# moire_v2_7.net
KiCad netlist of a schematic drawn in EAGLE
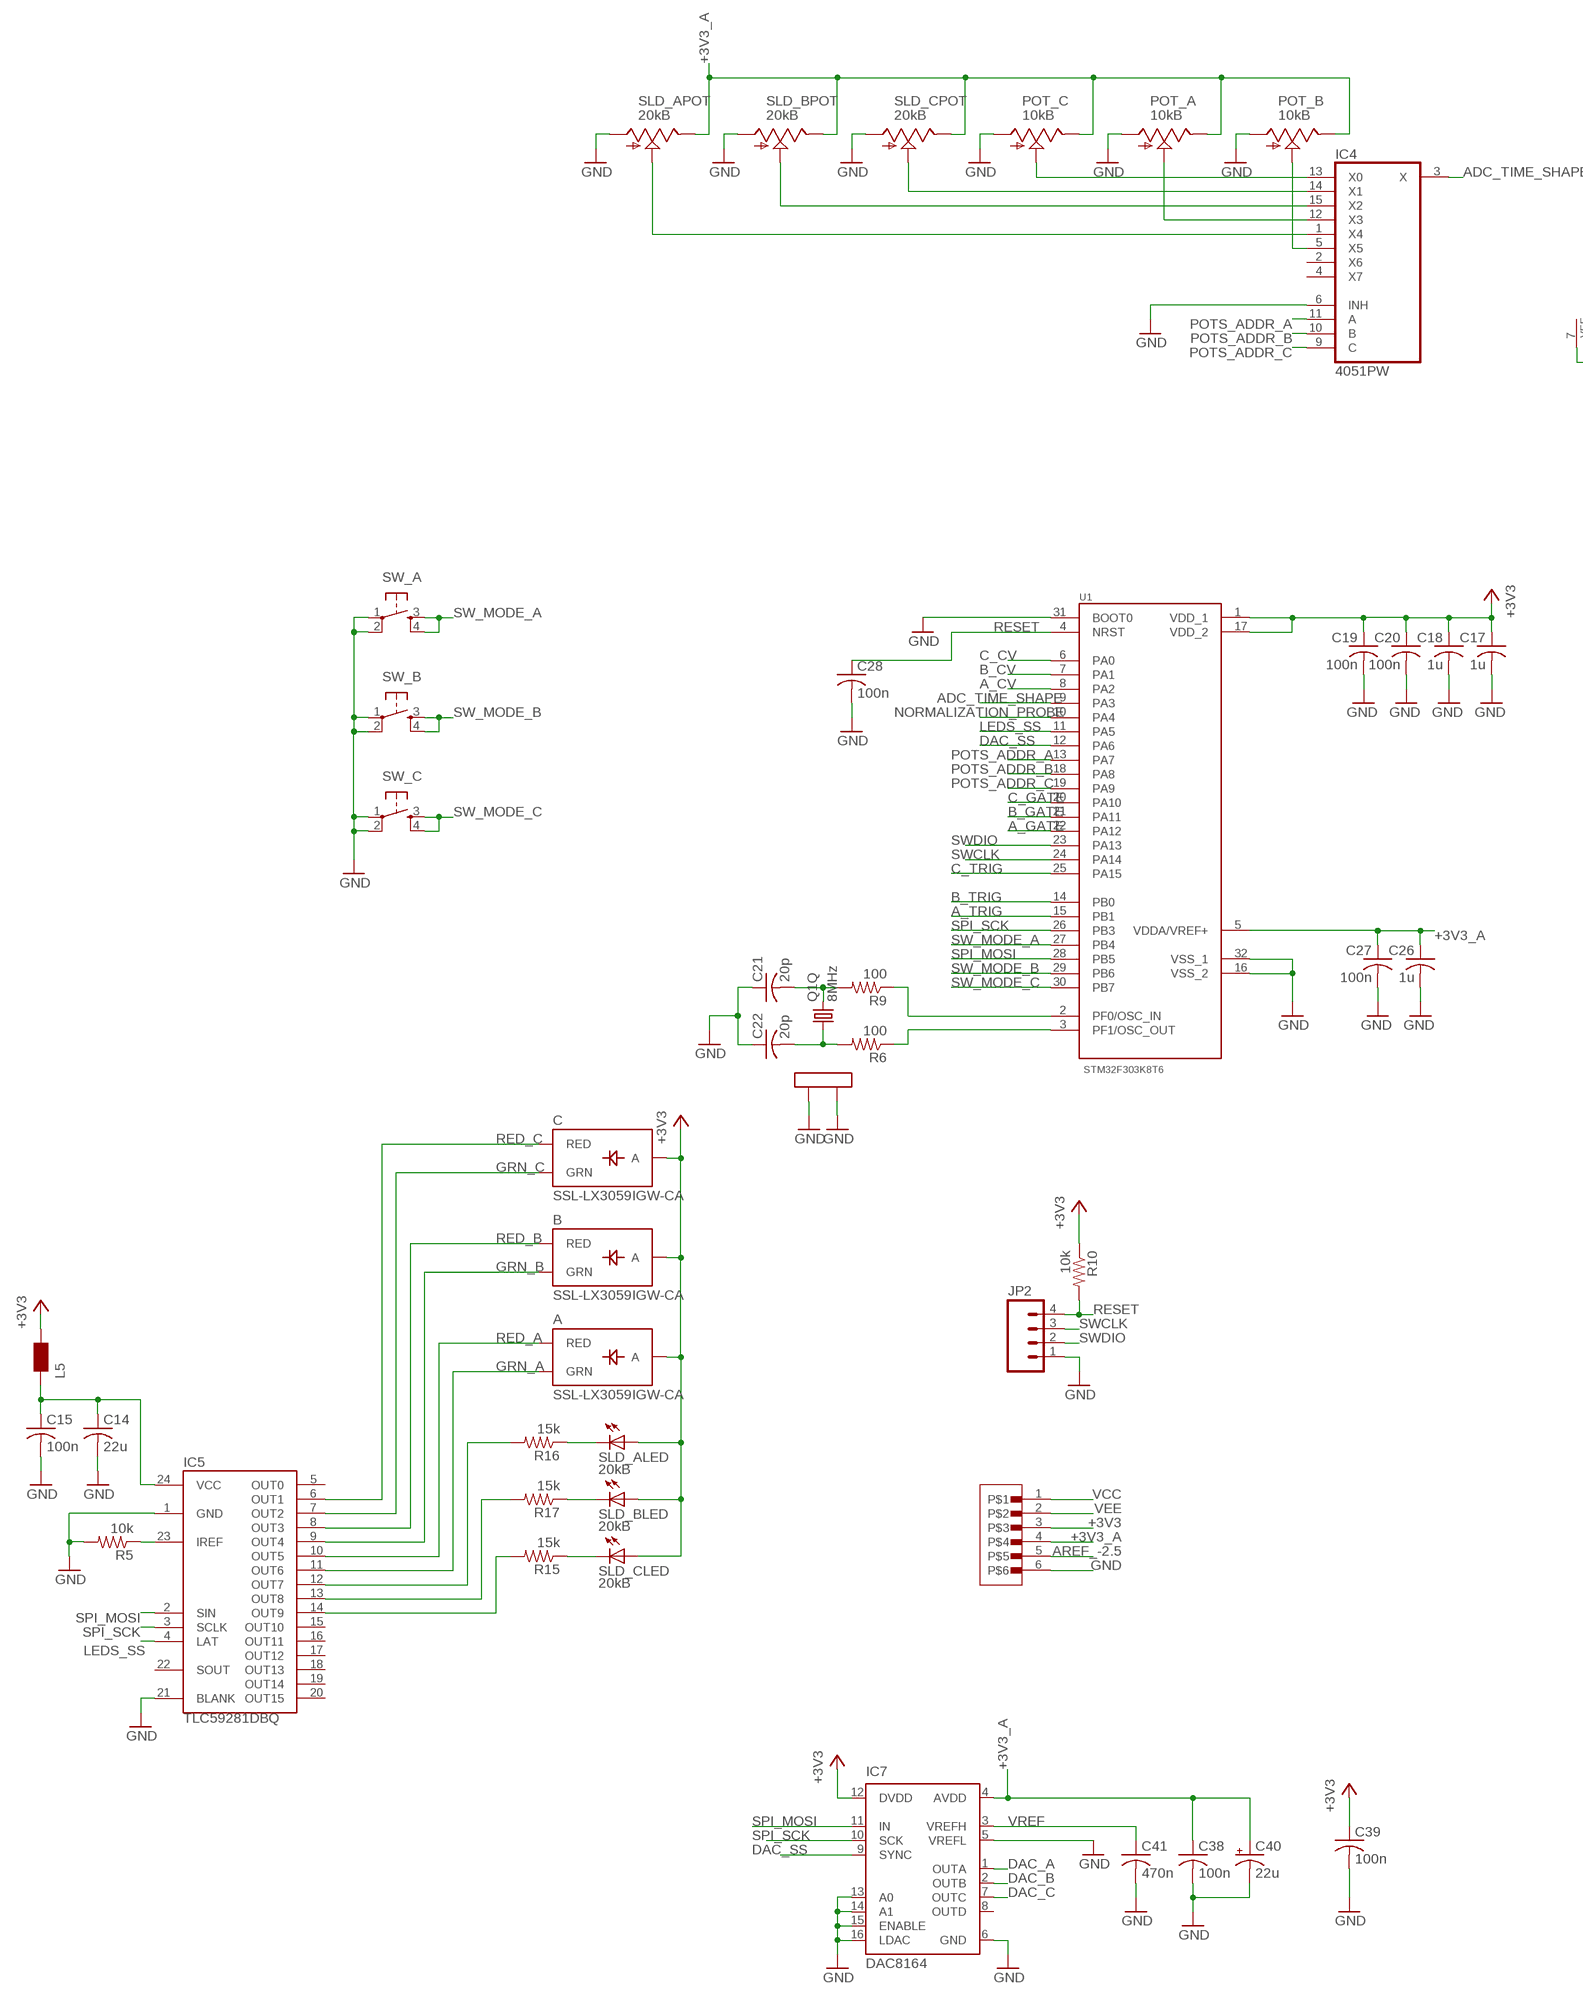
[diagram p0: schematic, sheet 1, part 1 of 2]
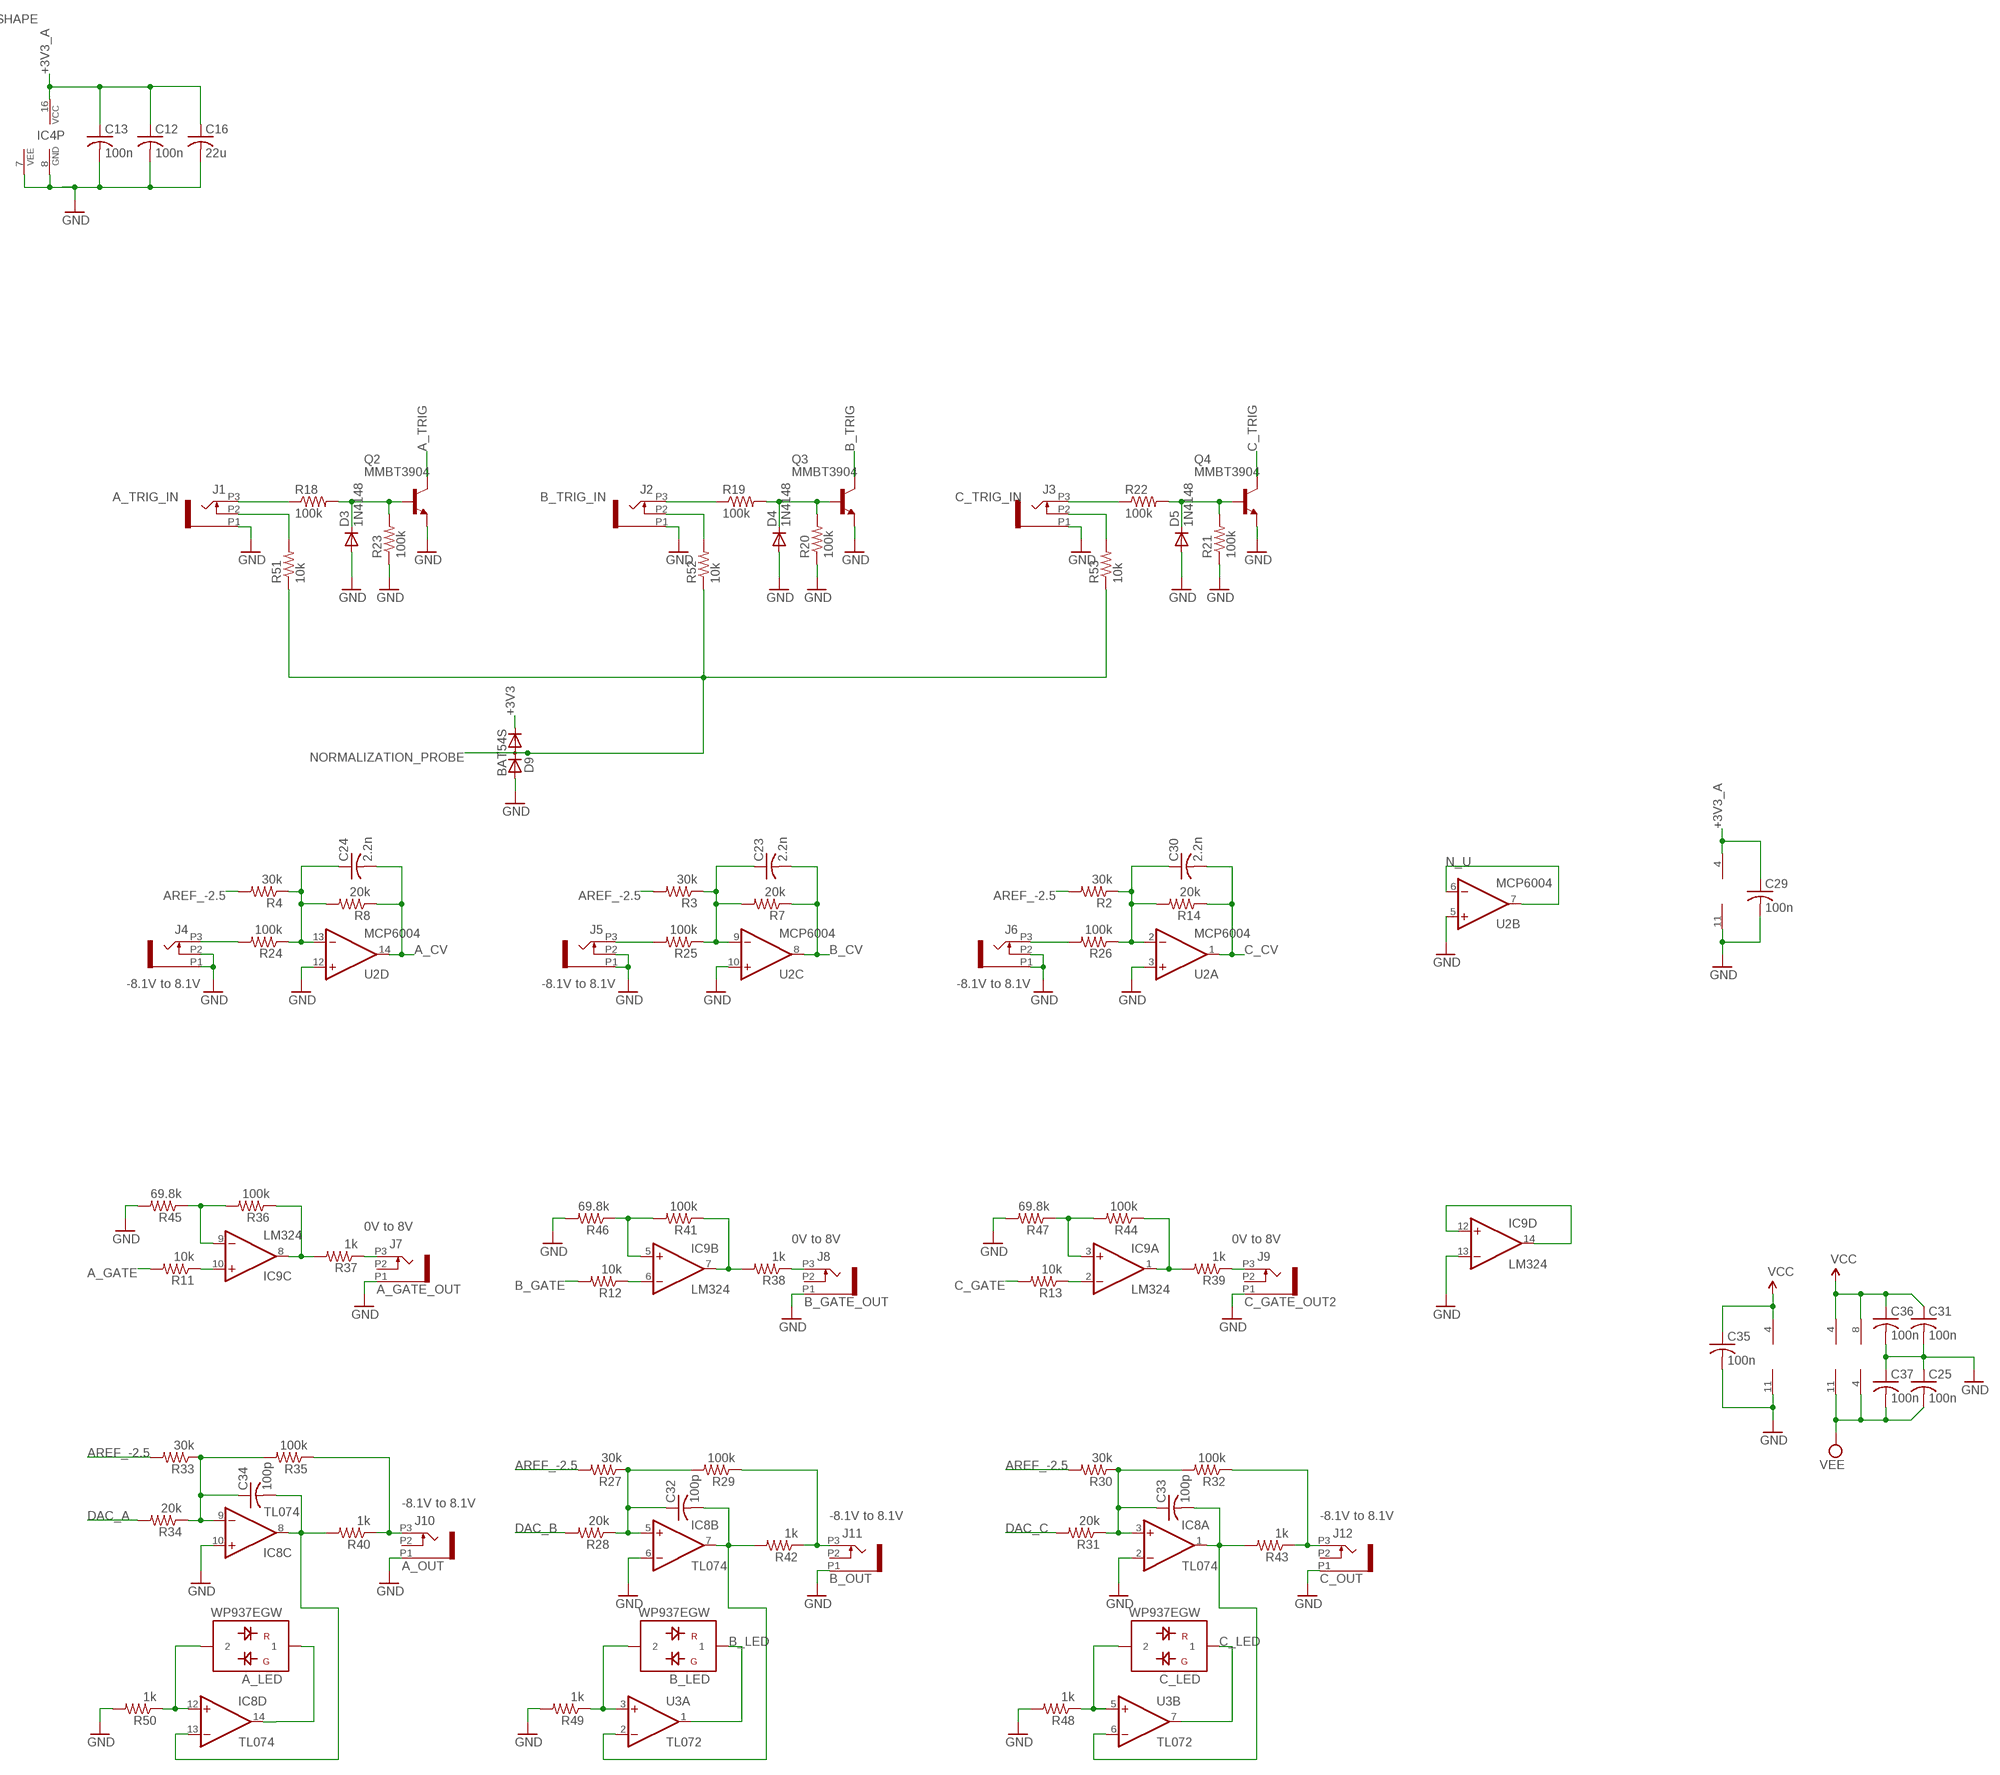
[diagram p1: schematic, sheet 1, part 2 of 2]
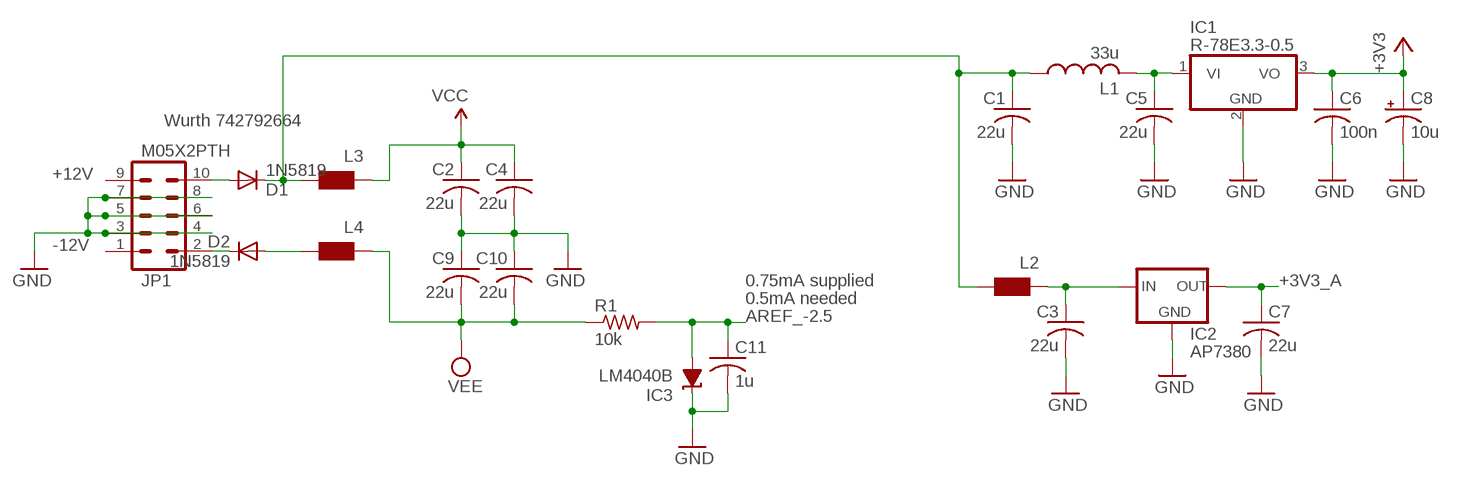
[diagram p2: schematic, sheet 2]

(export (version "E")
  (design (tool "Eeschema 10.0.6"))
  (components
    (comp (ref "A")
      (value "SSL-LX3059IGW-CA")
      (footprint "eagle-import:LED-BICOLOR-THROUGHHOLE-LUMEX")
      (libsource (lib "eagle-import") (part "LED-BICOLOR-THROUGHHOLE-CA"))
    )
    (comp (ref "A_LED")
      (value "WP937EGW")
      (footprint "eagle-import:LED3MM")
      (libsource (lib "eagle-import") (part "LED-BICOLOR-SHARED-THROUGHHOLE"))
    )
    (comp (ref "B")
      (value "SSL-LX3059IGW-CA")
      (footprint "eagle-import:LED-BICOLOR-THROUGHHOLE-LUMEX")
      (libsource (lib "eagle-import") (part "LED-BICOLOR-THROUGHHOLE-CA"))
    )
    (comp (ref "B_LED")
      (value "WP937EGW")
      (footprint "eagle-import:LED3MM")
      (libsource (lib "eagle-import") (part "LED-BICOLOR-SHARED-THROUGHHOLE"))
    )
    (comp (ref "C")
      (value "SSL-LX3059IGW-CA")
      (footprint "eagle-import:LED-BICOLOR-THROUGHHOLE-LUMEX")
      (libsource (lib "eagle-import") (part "LED-BICOLOR-THROUGHHOLE-CA"))
    )
    (comp (ref "C12")
      (value "100n")
      (footprint "eagle-import:RCL_C0603")
      (libsource (lib "eagle-import") (part "RCL_C-USC0603"))
    )
    (comp (ref "C13")
      (value "100n")
      (footprint "eagle-import:RCL_C0603")
      (libsource (lib "eagle-import") (part "RCL_C-USC0603"))
    )
    (comp (ref "C14")
      (value "22u")
      (footprint "eagle-import:RCL_C1206")
      (libsource (lib "eagle-import") (part "RCL_C-USC1206"))
    )
    (comp (ref "C15")
      (value "100n")
      (footprint "eagle-import:RCL_C0603")
      (libsource (lib "eagle-import") (part "RCL_C-USC0603"))
    )
    (comp (ref "C16")
      (value "22u")
      (footprint "eagle-import:RCL_C1206")
      (libsource (lib "eagle-import") (part "RCL_C-USC1206"))
    )
    (comp (ref "C17")
      (value "1u")
      (footprint "eagle-import:RCL_C0603")
      (libsource (lib "eagle-import") (part "RCL_C-USC0603"))
    )
    (comp (ref "C18")
      (value "1u")
      (footprint "eagle-import:RCL_C0603")
      (libsource (lib "eagle-import") (part "RCL_C-USC0603"))
    )
    (comp (ref "C19")
      (value "100n")
      (footprint "eagle-import:RCL_C0603")
      (libsource (lib "eagle-import") (part "RCL_C-USC0603"))
    )
    (comp (ref "C20")
      (value "100n")
      (footprint "eagle-import:RCL_C0603")
      (libsource (lib "eagle-import") (part "RCL_C-USC0603"))
    )
    (comp (ref "C21")
      (value "20p")
      (footprint "eagle-import:RCL_C0603")
      (libsource (lib "eagle-import") (part "RCL_C-USC0603"))
    )
    (comp (ref "C22")
      (value "20p")
      (footprint "eagle-import:RCL_C0603")
      (libsource (lib "eagle-import") (part "RCL_C-USC0603"))
    )
    (comp (ref "C23")
      (value "2.2n")
      (footprint "eagle-import:RCL_C0603")
      (libsource (lib "eagle-import") (part "RCL_C-USC0603"))
    )
    (comp (ref "C24")
      (value "2.2n")
      (footprint "eagle-import:RCL_C0603")
      (libsource (lib "eagle-import") (part "RCL_C-USC0603"))
    )
    (comp (ref "C25")
      (value "100n")
      (footprint "eagle-import:RCL_C0603")
      (libsource (lib "eagle-import") (part "RCL_C-USC0603"))
    )
    (comp (ref "C26")
      (value "1u")
      (footprint "eagle-import:RCL_C0603")
      (libsource (lib "eagle-import") (part "RCL_C-USC0603"))
    )
    (comp (ref "C27")
      (value "100n")
      (footprint "eagle-import:RCL_C0603")
      (libsource (lib "eagle-import") (part "RCL_C-USC0603"))
    )
    (comp (ref "C28")
      (value "100n")
      (footprint "eagle-import:RCL_C0603")
      (libsource (lib "eagle-import") (part "RCL_C-USC0603"))
    )
    (comp (ref "C29")
      (value "100n")
      (footprint "eagle-import:RCL_C0603")
      (libsource (lib "eagle-import") (part "RCL_C-USC0603"))
    )
    (comp (ref "C30")
      (value "2.2n")
      (footprint "eagle-import:RCL_C0603")
      (libsource (lib "eagle-import") (part "RCL_C-USC0603"))
    )
    (comp (ref "C31")
      (value "100n")
      (footprint "eagle-import:RCL_C0603")
      (libsource (lib "eagle-import") (part "RCL_C-USC0603"))
    )
    (comp (ref "C32")
      (value "100p")
      (footprint "eagle-import:RCL_C0603")
      (libsource (lib "eagle-import") (part "RCL_C-USC0603"))
    )
    (comp (ref "C33")
      (value "100p")
      (footprint "eagle-import:RCL_C0603")
      (libsource (lib "eagle-import") (part "RCL_C-USC0603"))
    )
    (comp (ref "C34")
      (value "100p")
      (footprint "eagle-import:RCL_C0603")
      (libsource (lib "eagle-import") (part "RCL_C-USC0603"))
    )
    (comp (ref "C35")
      (value "100n")
      (footprint "eagle-import:RCL_C0603")
      (libsource (lib "eagle-import") (part "RCL_C-USC0603"))
    )
    (comp (ref "C36")
      (value "100n")
      (footprint "eagle-import:RCL_C0603")
      (libsource (lib "eagle-import") (part "RCL_C-USC0603"))
    )
    (comp (ref "C37")
      (value "100n")
      (footprint "eagle-import:RCL_C0603")
      (libsource (lib "eagle-import") (part "RCL_C-USC0603"))
    )
    (comp (ref "C38")
      (value "100n")
      (footprint "eagle-import:C0603")
      (libsource (lib "eagle-import") (part "C-USC0603"))
    )
    (comp (ref "C39")
      (value "100n")
      (footprint "eagle-import:C0603")
      (libsource (lib "eagle-import") (part "C-USC0603"))
    )
    (comp (ref "C40")
      (value "22u")
      (footprint "eagle-import:PANASONIC_C")
      (libsource (lib "eagle-import") (part "CPOL-USC"))
    )
    (comp (ref "C41")
      (value "470n")
      (footprint "eagle-import:C0603")
      (libsource (lib "eagle-import") (part "C-USC0603"))
    )
    (comp (ref "C_LED")
      (value "WP937EGW")
      (footprint "eagle-import:LED3MM")
      (libsource (lib "eagle-import") (part "LED-BICOLOR-SHARED-THROUGHHOLE"))
    )
    (comp (ref "D3")
      (value "1N4148")
      (footprint "eagle-import:DIODE_SOD323-R")
      (libsource (lib "eagle-import") (part "DIODE_DIODE-SOD323-R"))
    )
    (comp (ref "D4")
      (value "1N4148")
      (footprint "eagle-import:DIODE_SOD323-R")
      (libsource (lib "eagle-import") (part "DIODE_DIODE-SOD323-R"))
    )
    (comp (ref "D5")
      (value "1N4148")
      (footprint "eagle-import:DIODE_SOD323-R")
      (libsource (lib "eagle-import") (part "DIODE_DIODE-SOD323-R"))
    )
    (comp (ref "D9")
      (value "BAT54S")
      (footprint "eagle-import:SOT23")
      (libsource (lib "eagle-import") (part "DIODE_2CACA-SOT23"))
    )
    (comp (ref "IC4")
      (value "4051PW")
      (footprint "eagle-import:TSSOP16_065")
      (libsource (lib "eagle-import") (part "4051PW"))
    )
    (comp (ref "IC5")
      (value "TLC59281DBQ")
      (footprint "eagle-import:TSSOP24_0635")
      (libsource (lib "eagle-import") (part "TLC59281DBQ"))
    )
    (comp (ref "IC7")
      (value "DAC8164")
      (footprint "eagle-import:SOP65P640X110-16N")
      (libsource (lib "eagle-import") (part "DAC8564"))
    )
    (comp (ref "IC8")
      (value "TL074")
      (footprint "eagle-import:TSSOP14_065")
      (libsource (lib "eagle-import") (part "TL074PW"))
    )
    (comp (ref "IC9")
      (value "LM324")
      (footprint "eagle-import:TSSOP14_065")
      (libsource (lib "eagle-import") (part "og-linear_TL074PW"))
    )
    (comp (ref "J1")
      (value "PJ301_THONKICONN6")
      (footprint "eagle-import:WQP_PJ_301M6")
      (libsource (lib "eagle-import") (part "PJ301_THONKICONN6"))
    )
    (comp (ref "J2")
      (value "PJ301_THONKICONN6")
      (footprint "eagle-import:WQP_PJ_301M6")
      (libsource (lib "eagle-import") (part "PJ301_THONKICONN6"))
    )
    (comp (ref "J3")
      (value "PJ301_THONKICONN6")
      (footprint "eagle-import:WQP_PJ_301M6")
      (libsource (lib "eagle-import") (part "PJ301_THONKICONN6"))
    )
    (comp (ref "J4")
      (value "PJ301_THONKICONN6")
      (footprint "eagle-import:WQP_PJ_301M6")
      (libsource (lib "eagle-import") (part "PJ301_THONKICONN6"))
    )
    (comp (ref "J5")
      (value "PJ301_THONKICONN6")
      (footprint "eagle-import:WQP_PJ_301M6")
      (libsource (lib "eagle-import") (part "PJ301_THONKICONN6"))
    )
    (comp (ref "J6")
      (value "PJ301_THONKICONN6")
      (footprint "eagle-import:WQP_PJ_301M6")
      (libsource (lib "eagle-import") (part "PJ301_THONKICONN6"))
    )
    (comp (ref "J7")
      (value "PJ301_THONKICONN6")
      (footprint "eagle-import:WQP_PJ_301M6")
      (libsource (lib "eagle-import") (part "PJ301_THONKICONN6"))
    )
    (comp (ref "J8")
      (value "PJ301_THONKICONN6")
      (footprint "eagle-import:WQP_PJ_301M6")
      (libsource (lib "eagle-import") (part "PJ301_THONKICONN6"))
    )
    (comp (ref "J9")
      (value "PJ301_THONKICONN6")
      (footprint "eagle-import:WQP_PJ_301M6")
      (libsource (lib "eagle-import") (part "PJ301_THONKICONN6"))
    )
    (comp (ref "J10")
      (value "PJ301_THONKICONN6")
      (footprint "eagle-import:WQP_PJ_301M6")
      (libsource (lib "eagle-import") (part "PJ301_THONKICONN6"))
    )
    (comp (ref "J11")
      (value "PJ301_THONKICONN6")
      (footprint "eagle-import:WQP_PJ_301M6")
      (libsource (lib "eagle-import") (part "PJ301_THONKICONN6"))
    )
    (comp (ref "J12")
      (value "PJ301_THONKICONN6")
      (footprint "eagle-import:WQP_PJ_301M6")
      (libsource (lib "eagle-import") (part "PJ301_THONKICONN6"))
    )
    (comp (ref "JP2")
      (value "M04PTH")
      (footprint "eagle-import:1X04")
      (libsource (lib "eagle-import") (part "M04PTH"))
    )
    (comp (ref "L5")
      (value "WE-CBF_0603")
      (footprint "eagle-import:0603")
      (libsource (lib "eagle-import") (part "WE-CBF_0603"))
    )
    (comp (ref "POT_A")
      (value "10kB")
      (footprint "eagle-import:ALPS_POT_VERTICAL")
      (libsource (lib "eagle-import") (part "POT_USVERTICAL"))
    )
    (comp (ref "POT_B")
      (value "10kB")
      (footprint "eagle-import:ALPS_POT_VERTICAL")
      (libsource (lib "eagle-import") (part "POT_USVERTICAL"))
    )
    (comp (ref "POT_C")
      (value "10kB")
      (footprint "eagle-import:ALPS_POT_VERTICAL")
      (libsource (lib "eagle-import") (part "POT_USVERTICAL"))
    )
    (comp (ref "Q1")
      (value "8MHz")
      (footprint "eagle-import:CTS406")
      (libsource (lib "eagle-import") (part "CRYSTAL"))
    )
    (comp (ref "Q2")
      (value "MMBT3904")
      (footprint "eagle-import:SOT23-BEC")
      (libsource (lib "eagle-import") (part "-NPN-SOT23-BECMMBT3904LT1"))
    )
    (comp (ref "Q3")
      (value "MMBT3904")
      (footprint "eagle-import:SOT23-BEC")
      (libsource (lib "eagle-import") (part "-NPN-SOT23-BECMMBT3904LT1"))
    )
    (comp (ref "Q4")
      (value "MMBT3904")
      (footprint "eagle-import:SOT23-BEC")
      (libsource (lib "eagle-import") (part "-NPN-SOT23-BECMMBT3904LT1"))
    )
    (comp (ref "R2")
      (value "30k")
      (footprint "eagle-import:RCL_R0603")
      (libsource (lib "eagle-import") (part "RCL_R-US_R0603"))
    )
    (comp (ref "R3")
      (value "30k")
      (footprint "eagle-import:RCL_R0603")
      (libsource (lib "eagle-import") (part "RCL_R-US_R0603"))
    )
    (comp (ref "R4")
      (value "30k")
      (footprint "eagle-import:RCL_R0603")
      (libsource (lib "eagle-import") (part "RCL_R-US_R0603"))
    )
    (comp (ref "R5")
      (value "10k")
      (footprint "eagle-import:RCL_R0603")
      (libsource (lib "eagle-import") (part "RCL_R-US_R0603"))
    )
    (comp (ref "R6")
      (value "100")
      (footprint "eagle-import:RCL_R0603")
      (libsource (lib "eagle-import") (part "RCL_R-US_R0603"))
    )
    (comp (ref "R7")
      (value "20k")
      (footprint "eagle-import:RCL_R0603")
      (libsource (lib "eagle-import") (part "RCL_R-US_R0603"))
    )
    (comp (ref "R8")
      (value "20k")
      (footprint "eagle-import:RCL_R0603")
      (libsource (lib "eagle-import") (part "RCL_R-US_R0603"))
    )
    (comp (ref "R9")
      (value "100")
      (footprint "eagle-import:RCL_R0603")
      (libsource (lib "eagle-import") (part "RCL_R-US_R0603"))
    )
    (comp (ref "R10")
      (value "10k")
      (footprint "eagle-import:RCL_R0603")
      (libsource (lib "eagle-import") (part "RCL_R-US_R0603"))
    )
    (comp (ref "R11")
      (value "10k")
      (footprint "eagle-import:RCL_R0603")
      (libsource (lib "eagle-import") (part "RCL_R-US_R0603"))
    )
    (comp (ref "R12")
      (value "10k")
      (footprint "eagle-import:RCL_R0603")
      (libsource (lib "eagle-import") (part "RCL_R-US_R0603"))
    )
    (comp (ref "R13")
      (value "10k")
      (footprint "eagle-import:RCL_R0603")
      (libsource (lib "eagle-import") (part "RCL_R-US_R0603"))
    )
    (comp (ref "R14")
      (value "20k")
      (footprint "eagle-import:RCL_R0603")
      (libsource (lib "eagle-import") (part "RCL_R-US_R0603"))
    )
    (comp (ref "R15")
      (value "15k")
      (footprint "eagle-import:RCL_R0603")
      (libsource (lib "eagle-import") (part "RCL_R-US_R0603"))
    )
    (comp (ref "R16")
      (value "15k")
      (footprint "eagle-import:RCL_R0603")
      (libsource (lib "eagle-import") (part "RCL_R-US_R0603"))
    )
    (comp (ref "R17")
      (value "15k")
      (footprint "eagle-import:RCL_R0603")
      (libsource (lib "eagle-import") (part "RCL_R-US_R0603"))
    )
    (comp (ref "R18")
      (value "100k")
      (footprint "eagle-import:RCL_R0603")
      (libsource (lib "eagle-import") (part "RCL_R-US_R0603"))
    )
    (comp (ref "R19")
      (value "100k")
      (footprint "eagle-import:RCL_R0603")
      (libsource (lib "eagle-import") (part "RCL_R-US_R0603"))
    )
    (comp (ref "R20")
      (value "100k")
      (footprint "eagle-import:RCL_R0603")
      (libsource (lib "eagle-import") (part "RCL_R-US_R0603"))
    )
    (comp (ref "R21")
      (value "100k")
      (footprint "eagle-import:RCL_R0603")
      (libsource (lib "eagle-import") (part "RCL_R-US_R0603"))
    )
    (comp (ref "R22")
      (value "100k")
      (footprint "eagle-import:RCL_R0603")
      (libsource (lib "eagle-import") (part "RCL_R-US_R0603"))
    )
    (comp (ref "R23")
      (value "100k")
      (footprint "eagle-import:RCL_R0603")
      (libsource (lib "eagle-import") (part "RCL_R-US_R0603"))
    )
    (comp (ref "R24")
      (value "100k")
      (footprint "eagle-import:RCL_R0603")
      (libsource (lib "eagle-import") (part "RCL_R-US_R0603"))
    )
    (comp (ref "R25")
      (value "100k")
      (footprint "eagle-import:RCL_R0603")
      (libsource (lib "eagle-import") (part "RCL_R-US_R0603"))
    )
    (comp (ref "R26")
      (value "100k")
      (footprint "eagle-import:RCL_R0603")
      (libsource (lib "eagle-import") (part "RCL_R-US_R0603"))
    )
    (comp (ref "R27")
      (value "30k")
      (footprint "eagle-import:RCL_R0603")
      (libsource (lib "eagle-import") (part "RCL_R-US_R0603"))
    )
    (comp (ref "R28")
      (value "20k")
      (footprint "eagle-import:RCL_R0603")
      (libsource (lib "eagle-import") (part "RCL_R-US_R0603"))
    )
    (comp (ref "R29")
      (value "100k")
      (footprint "eagle-import:RCL_R0603")
      (libsource (lib "eagle-import") (part "RCL_R-US_R0603"))
    )
    (comp (ref "R30")
      (value "30k")
      (footprint "eagle-import:RCL_R0603")
      (libsource (lib "eagle-import") (part "RCL_R-US_R0603"))
    )
    (comp (ref "R31")
      (value "20k")
      (footprint "eagle-import:RCL_R0603")
      (libsource (lib "eagle-import") (part "RCL_R-US_R0603"))
    )
    (comp (ref "R32")
      (value "100k")
      (footprint "eagle-import:RCL_R0603")
      (libsource (lib "eagle-import") (part "RCL_R-US_R0603"))
    )
    (comp (ref "R33")
      (value "30k")
      (footprint "eagle-import:RCL_R0603")
      (libsource (lib "eagle-import") (part "RCL_R-US_R0603"))
    )
    (comp (ref "R34")
      (value "20k")
      (footprint "eagle-import:RCL_R0603")
      (libsource (lib "eagle-import") (part "RCL_R-US_R0603"))
    )
    (comp (ref "R35")
      (value "100k")
      (footprint "eagle-import:RCL_R0603")
      (libsource (lib "eagle-import") (part "RCL_R-US_R0603"))
    )
    (comp (ref "R36")
      (value "100k")
      (footprint "eagle-import:RCL_R0603")
      (libsource (lib "eagle-import") (part "RCL_R-US_R0603"))
    )
    (comp (ref "R37")
      (value "1k")
      (footprint "eagle-import:RCL_R0603")
      (libsource (lib "eagle-import") (part "RCL_R-US_R0603"))
    )
    (comp (ref "R38")
      (value "1k")
      (footprint "eagle-import:RCL_R0603")
      (libsource (lib "eagle-import") (part "RCL_R-US_R0603"))
    )
    (comp (ref "R39")
      (value "1k")
      (footprint "eagle-import:RCL_R0603")
      (libsource (lib "eagle-import") (part "RCL_R-US_R0603"))
    )
    (comp (ref "R40")
      (value "1k")
      (footprint "eagle-import:RCL_R0603")
      (libsource (lib "eagle-import") (part "RCL_R-US_R0603"))
    )
    (comp (ref "R41")
      (value "100k")
      (footprint "eagle-import:RCL_R0603")
      (libsource (lib "eagle-import") (part "RCL_R-US_R0603"))
    )
    (comp (ref "R42")
      (value "1k")
      (footprint "eagle-import:RCL_R0603")
      (libsource (lib "eagle-import") (part "RCL_R-US_R0603"))
    )
    (comp (ref "R43")
      (value "1k")
      (footprint "eagle-import:RCL_R0603")
      (libsource (lib "eagle-import") (part "RCL_R-US_R0603"))
    )
    (comp (ref "R44")
      (value "100k")
      (footprint "eagle-import:RCL_R0603")
      (libsource (lib "eagle-import") (part "RCL_R-US_R0603"))
    )
    (comp (ref "R45")
      (value "69.8k")
      (footprint "eagle-import:RCL_R0603")
      (libsource (lib "eagle-import") (part "RCL_R-US_R0603"))
    )
    (comp (ref "R46")
      (value "69.8k")
      (footprint "eagle-import:RCL_R0603")
      (libsource (lib "eagle-import") (part "RCL_R-US_R0603"))
    )
    (comp (ref "R47")
      (value "69.8k")
      (footprint "eagle-import:RCL_R0603")
      (libsource (lib "eagle-import") (part "RCL_R-US_R0603"))
    )
    (comp (ref "R48")
      (value "1k")
      (footprint "eagle-import:RCL_R0603")
      (libsource (lib "eagle-import") (part "RCL_R-US_R0603"))
    )
    (comp (ref "R49")
      (value "1k")
      (footprint "eagle-import:RCL_R0603")
      (libsource (lib "eagle-import") (part "RCL_R-US_R0603"))
    )
    (comp (ref "R50")
      (value "1k")
      (footprint "eagle-import:RCL_R0603")
      (libsource (lib "eagle-import") (part "RCL_R-US_R0603"))
    )
    (comp (ref "R51")
      (value "10k")
      (footprint "eagle-import:RCL_R0603")
      (libsource (lib "eagle-import") (part "RCL_R-US_R0603"))
    )
    (comp (ref "R52")
      (value "10k")
      (footprint "eagle-import:RCL_R0603")
      (libsource (lib "eagle-import") (part "RCL_R-US_R0603"))
    )
    (comp (ref "R53")
      (value "10k")
      (footprint "eagle-import:RCL_R0603")
      (libsource (lib "eagle-import") (part "RCL_R-US_R0603"))
    )
    (comp (ref "SLD_A")
      (value "20kB")
      (footprint "eagle-import:BOURNS_SLIDER")
      (libsource (lib "eagle-import") (part "BOURNS_SLIDER"))
    )
    (comp (ref "SLD_B")
      (value "20kB")
      (footprint "eagle-import:BOURNS_SLIDER")
      (libsource (lib "eagle-import") (part "BOURNS_SLIDER"))
    )
    (comp (ref "SLD_C")
      (value "20kB")
      (footprint "eagle-import:BOURNS_SLIDER")
      (libsource (lib "eagle-import") (part "BOURNS_SLIDER"))
    )
    (comp (ref "SW_A")
      (value "TAC_SWITCHPTH")
      (footprint "eagle-import:TACTILE-PTH")
      (libsource (lib "eagle-import") (part "TAC_SWITCHPTH"))
    )
    (comp (ref "SW_B")
      (value "TAC_SWITCHPTH")
      (footprint "eagle-import:TACTILE-PTH")
      (libsource (lib "eagle-import") (part "TAC_SWITCHPTH"))
    )
    (comp (ref "SW_C")
      (value "TAC_SWITCHPTH")
      (footprint "eagle-import:TACTILE-PTH")
      (libsource (lib "eagle-import") (part "TAC_SWITCHPTH"))
    )
    (comp (ref "U$1")
      (value "1X6-SMD-TESTPAD")
      (footprint "eagle-import:6X1-SMD-TESTPAD")
      (libsource (lib "eagle-import") (part "1X6-SMD-TESTPAD"))
    )
    (comp (ref "U1")
      (value "STM32F303K8T6")
      (footprint "eagle-import:QFP80P900X900X160-32N")
      (fields (field (name "MF") "STMicroelectronics"))
      (libsource (lib "eagle-import") (part "STM32F303K8T6"))
    )
    (comp (ref "U2")
      (value "MCP6004")
      (footprint "eagle-import:SO14")
      (libsource (lib "eagle-import") (part "MCP6004_SMD"))
    )
    (comp (ref "U3")
      (value "TL072")
      (footprint "eagle-import:TSSOP-8")
      (libsource (lib "eagle-import") (part "TL072TSSOP"))
    )
    (comp (ref "C1")
      (value "22u")
      (footprint "eagle-import:RCL_C1206")
      (libsource (lib "eagle-import") (part "RCL_C-USC1206"))
    )
    (comp (ref "C2")
      (value "22u")
      (footprint "eagle-import:RCL_C1206")
      (libsource (lib "eagle-import") (part "RCL_C-USC1206"))
    )
    (comp (ref "C3")
      (value "22u")
      (footprint "eagle-import:RCL_C1206")
      (libsource (lib "eagle-import") (part "RCL_C-USC1206"))
    )
    (comp (ref "C4")
      (value "22u")
      (footprint "eagle-import:RCL_C1206")
      (libsource (lib "eagle-import") (part "RCL_C-USC1206"))
    )
    (comp (ref "C5")
      (value "22u")
      (footprint "eagle-import:RCL_C1206")
      (libsource (lib "eagle-import") (part "RCL_C-USC1206"))
    )
    (comp (ref "C6")
      (value "100n")
      (footprint "eagle-import:RCL_C0603")
      (libsource (lib "eagle-import") (part "RCL_C-USC0603"))
    )
    (comp (ref "C7")
      (value "22u")
      (footprint "eagle-import:RCL_C1206")
      (libsource (lib "eagle-import") (part "RCL_C-USC1206"))
    )
    (comp (ref "C8")
      (value "10u")
      (footprint "eagle-import:RCL_PANASONIC_A")
      (libsource (lib "eagle-import") (part "RCL_CPOL-USA"))
    )
    (comp (ref "C9")
      (value "22u")
      (footprint "eagle-import:RCL_C1206")
      (libsource (lib "eagle-import") (part "RCL_C-USC1206"))
    )
    (comp (ref "C10")
      (value "22u")
      (footprint "eagle-import:RCL_C1206")
      (libsource (lib "eagle-import") (part "RCL_C-USC1206"))
    )
    (comp (ref "C11")
      (value "1u")
      (footprint "eagle-import:RCL_C0603")
      (libsource (lib "eagle-import") (part "RCL_C-USC0603"))
    )
    (comp (ref "D1")
      (value "1N5819")
      (footprint "eagle-import:DIODE_SOD123")
      (libsource (lib "eagle-import") (part "DIODE_DIODE-SOD123"))
    )
    (comp (ref "D2")
      (value "1N5819")
      (footprint "eagle-import:DIODE_SOD123")
      (libsource (lib "eagle-import") (part "DIODE_DIODE-SOD123"))
    )
    (comp (ref "IC1")
      (value "R-78E3.3-0.5")
      (footprint "eagle-import:WE78")
      (libsource (lib "eagle-import") (part "WE173950378"))
    )
    (comp (ref "IC2")
      (value "AP7380")
      (footprint "eagle-import:SOT89")
      (libsource (lib "eagle-import") (part "AP7380"))
    )
    (comp (ref "IC3")
      (value "LM4040B")
      (footprint "eagle-import:DBZ_R-PDSO-G3")
      (libsource (lib "eagle-import") (part "LM4041DBZB12"))
    )
    (comp (ref "JP1")
      (value "M05X2PTH")
      (footprint "eagle-import:2X5-PTH")
      (libsource (lib "eagle-import") (part "M05X2PTH"))
    )
    (comp (ref "L1")
      (value "33u")
      (footprint "eagle-import:L2012C")
      (libsource (lib "eagle-import") (part "L-USL2012C"))
    )
    (comp (ref "L2")
      (value "WE-CBF_0603")
      (footprint "eagle-import:0603")
      (libsource (lib "eagle-import") (part "WE-CBF_0603"))
    )
    (comp (ref "L3")
      (value "WE-CBF_0603")
      (footprint "eagle-import:0603")
      (libsource (lib "eagle-import") (part "WE-CBF_0603"))
    )
    (comp (ref "L4")
      (value "WE-CBF_0603")
      (footprint "eagle-import:0603")
      (libsource (lib "eagle-import") (part "WE-CBF_0603"))
    )
    (comp (ref "R1")
      (value "10k")
      (footprint "eagle-import:RCL_R0603")
      (libsource (lib "eagle-import") (part "RCL_R-US_R0603"))
    )
  )
  (nets
    (net (code "1") (name "+3V3") (class "Default")
      (node (ref "A") (pin "A") (pinfunction "A_A") (pintype "bidirectional"))
      (node (ref "B") (pin "A") (pinfunction "A_A") (pintype "bidirectional"))
      (node (ref "C") (pin "A") (pinfunction "A_A") (pintype "bidirectional"))
      (node (ref "C17") (pin "1") (pinfunction "1_1") (pintype "passive"))
      (node (ref "C18") (pin "1") (pinfunction "1_1") (pintype "passive"))
      (node (ref "C19") (pin "1") (pinfunction "1_1") (pintype "passive"))
      (node (ref "C20") (pin "1") (pinfunction "1_1") (pintype "passive"))
      (node (ref "C39") (pin "1") (pinfunction "1_1") (pintype "passive"))
      (node (ref "C6") (pin "1") (pinfunction "1_1") (pintype "passive"))
      (node (ref "C8") (pin "+") (pinfunction "+_+") (pintype "passive"))
      (node (ref "D9") (pin "2") (pinfunction "C_2") (pintype "passive"))
      (node (ref "IC1") (pin "3") (pinfunction "VO_3") (pintype "passive"))
      (node (ref "IC7") (pin "12") (pinfunction "DVDD_12") (pintype "power_in"))
      (node (ref "L5") (pin "2") (pinfunction "2_2") (pintype "passive"))
      (node (ref "R10") (pin "1") (pinfunction "1_1") (pintype "passive"))
      (node (ref "SLD_A") (pin "B") (pinfunction "A_B") (pintype "passive"))
      (node (ref "SLD_B") (pin "B") (pinfunction "A_B") (pintype "passive"))
      (node (ref "SLD_C") (pin "B") (pinfunction "A_B") (pintype "passive"))
      (node (ref "U$1") (pin "3") (pinfunction "P$3_3") (pintype "bidirectional"))
      (node (ref "U1") (pin "1") (pinfunction "VDD_1_1") (pintype "power_in"))
      (node (ref "U1") (pin "17") (pinfunction "VDD_2_17") (pintype "power_in"))
    )
    (net (code "2") (name "+3V3_A") (class "Default")
      (node (ref "C12") (pin "1") (pinfunction "1_1") (pintype "passive"))
      (node (ref "C13") (pin "1") (pinfunction "1_1") (pintype "passive"))
      (node (ref "C16") (pin "1") (pinfunction "1_1") (pintype "passive"))
      (node (ref "C26") (pin "1") (pinfunction "1_1") (pintype "passive"))
      (node (ref "C27") (pin "1") (pinfunction "1_1") (pintype "passive"))
      (node (ref "C29") (pin "1") (pinfunction "1_1") (pintype "passive"))
      (node (ref "C38") (pin "1") (pinfunction "1_1") (pintype "passive"))
      (node (ref "C40") (pin "+") (pinfunction "+_+") (pintype "passive"))
      (node (ref "C7") (pin "1") (pinfunction "1_1") (pintype "passive"))
      (node (ref "IC2") (pin "3") (pinfunction "OUT_3") (pintype "passive"))
      (node (ref "IC4") (pin "16") (pinfunction "VCC_16") (pintype "power_in"))
      (node (ref "IC7") (pin "4") (pinfunction "AVDD_4") (pintype "power_in"))
      (node (ref "POT_A") (pin "P$1") (pinfunction "E_P$1") (pintype "passive"))
      (node (ref "POT_B") (pin "P$1") (pinfunction "E_P$1") (pintype "passive"))
      (node (ref "POT_C") (pin "P$1") (pinfunction "E_P$1") (pintype "passive"))
      (node (ref "SLD_A") (pin "3") (pinfunction "E_3") (pintype "passive"))
      (node (ref "SLD_B") (pin "3") (pinfunction "E_3") (pintype "passive"))
      (node (ref "SLD_C") (pin "3") (pinfunction "E_3") (pintype "passive"))
      (node (ref "U$1") (pin "4") (pinfunction "P$4_4") (pintype "bidirectional"))
      (node (ref "U1") (pin "5") (pinfunction "VDDA/VREF+_5") (pintype "power_in"))
      (node (ref "U2") (pin "4") (pinfunction "V+_4") (pintype "power_in"))
    )
    (net (code "3") (name "+12V") (class "Default")
      (node (ref "D1") (pin "A") (pinfunction "A_A") (pintype "passive"))
      (node (ref "JP1") (pin "10") (pinfunction "10_10") (pintype "passive"))
      (node (ref "JP1") (pin "9") (pinfunction "9_9") (pintype "passive"))
    )
    (net (code "4") (name "-12V") (class "Default")
      (node (ref "D2") (pin "C") (pinfunction "C_C") (pintype "passive"))
      (node (ref "JP1") (pin "1") (pinfunction "1_1") (pintype "passive"))
      (node (ref "JP1") (pin "2") (pinfunction "2_2") (pintype "passive"))
    )
    (net (code "5") (name "ADC_TIME_SHAPE") (class "Default")
      (node (ref "IC4") (pin "3") (pinfunction "X_3") (pintype "bidirectional"))
      (node (ref "U1") (pin "9") (pinfunction "PA3_9") (pintype "bidirectional"))
    )
    (net (code "6") (name "AREF_-2.5") (class "Default")
      (node (ref "C11") (pin "1") (pinfunction "1_1") (pintype "passive"))
      (node (ref "IC3") (pin "2") (pinfunction "A_2") (pintype "passive"))
      (node (ref "R1") (pin "2") (pinfunction "2_2") (pintype "passive"))
      (node (ref "R2") (pin "2") (pinfunction "2_2") (pintype "passive"))
      (node (ref "R27") (pin "2") (pinfunction "2_2") (pintype "passive"))
      (node (ref "R3") (pin "2") (pinfunction "2_2") (pintype "passive"))
      (node (ref "R30") (pin "2") (pinfunction "2_2") (pintype "passive"))
      (node (ref "R33") (pin "2") (pinfunction "2_2") (pintype "passive"))
      (node (ref "R4") (pin "2") (pinfunction "2_2") (pintype "passive"))
      (node (ref "U$1") (pin "5") (pinfunction "P$5_5") (pintype "bidirectional"))
    )
    (net (code "7") (name "A_CV") (class "Default")
      (node (ref "C24") (pin "2") (pinfunction "2_2") (pintype "passive"))
      (node (ref "R8") (pin "1") (pinfunction "1_1") (pintype "passive"))
      (node (ref "U1") (pin "8") (pinfunction "PA2_8") (pintype "bidirectional"))
      (node (ref "U2") (pin "14") (pinfunction "OUT_14") (pintype "output"))
    )
    (net (code "8") (name "A_GATE") (class "Default")
      (node (ref "R11") (pin "2") (pinfunction "2_2") (pintype "passive"))
      (node (ref "U1") (pin "22") (pinfunction "PA12_22") (pintype "bidirectional"))
    )
    (net (code "9") (name "A_GATE_OUT") (class "Default")
      (node (ref "J7") (pin "P3") (pinfunction "3_P3") (pintype "passive"))
      (node (ref "R37") (pin "1") (pinfunction "1_1") (pintype "passive"))
    )
    (net (code "10") (name "A_OUT") (class "Default")
      (node (ref "J10") (pin "P3") (pinfunction "3_P3") (pintype "passive"))
      (node (ref "R35") (pin "1") (pinfunction "1_1") (pintype "passive"))
      (node (ref "R40") (pin "1") (pinfunction "1_1") (pintype "passive"))
    )
    (net (code "11") (name "A_TRIG") (class "Default")
      (node (ref "Q2") (pin "C") (pinfunction "C_C") (pintype "passive"))
      (node (ref "U1") (pin "15") (pinfunction "PB1_15") (pintype "bidirectional"))
    )
    (net (code "12") (name "A_TRIG_IN") (class "Default")
      (node (ref "J1") (pin "P3") (pinfunction "3_P3") (pintype "passive"))
      (node (ref "R18") (pin "1") (pinfunction "1_1") (pintype "passive"))
    )
    (net (code "13") (name "B_CV") (class "Default")
      (node (ref "C23") (pin "2") (pinfunction "2_2") (pintype "passive"))
      (node (ref "R7") (pin "1") (pinfunction "1_1") (pintype "passive"))
      (node (ref "U1") (pin "7") (pinfunction "PA1_7") (pintype "bidirectional"))
      (node (ref "U2") (pin "8") (pinfunction "OUT_8") (pintype "output"))
    )
    (net (code "14") (name "B_GATE") (class "Default")
      (node (ref "R12") (pin "2") (pinfunction "2_2") (pintype "passive"))
      (node (ref "U1") (pin "21") (pinfunction "PA11_21") (pintype "bidirectional"))
    )
    (net (code "15") (name "B_GATE_OUT") (class "Default")
      (node (ref "J8") (pin "P3") (pinfunction "3_P3") (pintype "passive"))
      (node (ref "R38") (pin "1") (pinfunction "1_1") (pintype "passive"))
    )
    (net (code "16") (name "B_LED") (class "Default")
      (node (ref "B_LED") (pin "1") (pinfunction "1_1") (pintype "bidirectional"))
      (node (ref "U3") (pin "1") (pinfunction "OUT_1") (pintype "output"))
    )
    (net (code "17") (name "B_OUT") (class "Default")
      (node (ref "J11") (pin "P3") (pinfunction "3_P3") (pintype "passive"))
      (node (ref "R29") (pin "1") (pinfunction "1_1") (pintype "passive"))
      (node (ref "R42") (pin "1") (pinfunction "1_1") (pintype "passive"))
    )
    (net (code "18") (name "B_TRIG") (class "Default")
      (node (ref "Q3") (pin "C") (pinfunction "C_C") (pintype "passive"))
      (node (ref "U1") (pin "14") (pinfunction "PB0_14") (pintype "bidirectional"))
    )
    (net (code "19") (name "B_TRIG_IN") (class "Default")
      (node (ref "J2") (pin "P3") (pinfunction "3_P3") (pintype "passive"))
      (node (ref "R19") (pin "1") (pinfunction "1_1") (pintype "passive"))
    )
    (net (code "20") (name "C_CV") (class "Default")
      (node (ref "C30") (pin "2") (pinfunction "2_2") (pintype "passive"))
      (node (ref "R14") (pin "1") (pinfunction "1_1") (pintype "passive"))
      (node (ref "U1") (pin "6") (pinfunction "PA0_6") (pintype "bidirectional"))
      (node (ref "U2") (pin "1") (pinfunction "OUT_1") (pintype "output"))
    )
    (net (code "21") (name "C_GATE") (class "Default")
      (node (ref "R13") (pin "2") (pinfunction "2_2") (pintype "passive"))
      (node (ref "U1") (pin "20") (pinfunction "PA10_20") (pintype "bidirectional"))
    )
    (net (code "22") (name "C_GATE_OUT2") (class "Default")
      (node (ref "J9") (pin "P3") (pinfunction "3_P3") (pintype "passive"))
      (node (ref "R39") (pin "1") (pinfunction "1_1") (pintype "passive"))
    )
    (net (code "23") (name "C_LED") (class "Default")
      (node (ref "C_LED") (pin "1") (pinfunction "1_1") (pintype "bidirectional"))
      (node (ref "U3") (pin "7") (pinfunction "OUT_7") (pintype "output"))
    )
    (net (code "24") (name "C_OUT") (class "Default")
      (node (ref "J12") (pin "P3") (pinfunction "3_P3") (pintype "passive"))
      (node (ref "R32") (pin "1") (pinfunction "1_1") (pintype "passive"))
      (node (ref "R43") (pin "1") (pinfunction "1_1") (pintype "passive"))
    )
    (net (code "25") (name "C_TRIG") (class "Default")
      (node (ref "Q4") (pin "C") (pinfunction "C_C") (pintype "passive"))
      (node (ref "U1") (pin "25") (pinfunction "PA15_25") (pintype "bidirectional"))
    )
    (net (code "26") (name "C_TRIG_IN") (class "Default")
      (node (ref "J3") (pin "P3") (pinfunction "3_P3") (pintype "passive"))
      (node (ref "R22") (pin "1") (pinfunction "1_1") (pintype "passive"))
    )
    (net (code "27") (name "DAC_A") (class "Default")
      (node (ref "IC7") (pin "1") (pinfunction "OUTA_1") (pintype "output"))
      (node (ref "R34") (pin "2") (pinfunction "2_2") (pintype "passive"))
    )
    (net (code "28") (name "DAC_B") (class "Default")
      (node (ref "IC7") (pin "2") (pinfunction "OUTB_2") (pintype "output"))
      (node (ref "R28") (pin "2") (pinfunction "2_2") (pintype "passive"))
    )
    (net (code "29") (name "DAC_C") (class "Default")
      (node (ref "IC7") (pin "7") (pinfunction "OUTC_7") (pintype "output"))
      (node (ref "R31") (pin "2") (pinfunction "2_2") (pintype "passive"))
    )
    (net (code "30") (name "DAC_SS") (class "Default")
      (node (ref "IC7") (pin "9") (pinfunction "SYNC_9") (pintype "input"))
      (node (ref "U1") (pin "12") (pinfunction "PA6_12") (pintype "bidirectional"))
    )
    (net (code "31") (name "GND") (class "Default")
      (node (ref "C1") (pin "2") (pinfunction "2_2") (pintype "passive"))
      (node (ref "C10") (pin "1") (pinfunction "1_1") (pintype "passive"))
      (node (ref "C11") (pin "2") (pinfunction "2_2") (pintype "passive"))
      (node (ref "C12") (pin "2") (pinfunction "2_2") (pintype "passive"))
      (node (ref "C13") (pin "2") (pinfunction "2_2") (pintype "passive"))
      (node (ref "C14") (pin "2") (pinfunction "2_2") (pintype "passive"))
      (node (ref "C15") (pin "2") (pinfunction "2_2") (pintype "passive"))
      (node (ref "C16") (pin "2") (pinfunction "2_2") (pintype "passive"))
      (node (ref "C17") (pin "2") (pinfunction "2_2") (pintype "passive"))
      (node (ref "C18") (pin "2") (pinfunction "2_2") (pintype "passive"))
      (node (ref "C19") (pin "2") (pinfunction "2_2") (pintype "passive"))
      (node (ref "C2") (pin "2") (pinfunction "2_2") (pintype "passive"))
      (node (ref "C20") (pin "2") (pinfunction "2_2") (pintype "passive"))
      (node (ref "C21") (pin "1") (pinfunction "1_1") (pintype "passive"))
      (node (ref "C22") (pin "1") (pinfunction "1_1") (pintype "passive"))
      (node (ref "C25") (pin "1") (pinfunction "1_1") (pintype "passive"))
      (node (ref "C26") (pin "2") (pinfunction "2_2") (pintype "passive"))
      (node (ref "C27") (pin "2") (pinfunction "2_2") (pintype "passive"))
      (node (ref "C28") (pin "2") (pinfunction "2_2") (pintype "passive"))
      (node (ref "C29") (pin "2") (pinfunction "2_2") (pintype "passive"))
      (node (ref "C3") (pin "2") (pinfunction "2_2") (pintype "passive"))
      (node (ref "C31") (pin "2") (pinfunction "2_2") (pintype "passive"))
      (node (ref "C35") (pin "2") (pinfunction "2_2") (pintype "passive"))
      (node (ref "C36") (pin "2") (pinfunction "2_2") (pintype "passive"))
      (node (ref "C37") (pin "1") (pinfunction "1_1") (pintype "passive"))
      (node (ref "C38") (pin "2") (pinfunction "2_2") (pintype "passive"))
      (node (ref "C39") (pin "2") (pinfunction "2_2") (pintype "passive"))
      (node (ref "C4") (pin "2") (pinfunction "2_2") (pintype "passive"))
      (node (ref "C40") (pin "-") (pinfunction "-_-") (pintype "passive"))
      (node (ref "C41") (pin "2") (pinfunction "2_2") (pintype "passive"))
      (node (ref "C5") (pin "2") (pinfunction "2_2") (pintype "passive"))
      (node (ref "C6") (pin "2") (pinfunction "2_2") (pintype "passive"))
      (node (ref "C7") (pin "2") (pinfunction "2_2") (pintype "passive"))
      (node (ref "C8") (pin "-") (pinfunction "-_-") (pintype "passive"))
      (node (ref "C9") (pin "1") (pinfunction "1_1") (pintype "passive"))
      (node (ref "D3") (pin "A") (pinfunction "A_A") (pintype "passive"))
      (node (ref "D4") (pin "A") (pinfunction "A_A") (pintype "passive"))
      (node (ref "D5") (pin "A") (pinfunction "A_A") (pintype "passive"))
      (node (ref "D9") (pin "1") (pinfunction "A_1") (pintype "passive"))
      (node (ref "IC1") (pin "2") (pinfunction "GND_2") (pintype "passive"))
      (node (ref "IC2") (pin "1") (pinfunction "GND_1") (pintype "input"))
      (node (ref "IC3") (pin "1") (pinfunction "C_1") (pintype "passive"))
      (node (ref "IC4") (pin "6") (pinfunction "INH_6") (pintype "input"))
      (node (ref "IC4") (pin "7") (pinfunction "VEE_7") (pintype "power_in"))
      (node (ref "IC4") (pin "8") (pinfunction "GND_8") (pintype "power_in"))
      (node (ref "IC5") (pin "1") (pinfunction "GND_1") (pintype "bidirectional"))
      (node (ref "IC5") (pin "21") (pinfunction "BLANK_21") (pintype "bidirectional"))
      (node (ref "IC7") (pin "13") (pinfunction "A0_13") (pintype "input"))
      (node (ref "IC7") (pin "14") (pinfunction "A1_14") (pintype "input"))
      (node (ref "IC7") (pin "15") (pinfunction "ENABLE_15") (pintype "input"))
      (node (ref "IC7") (pin "16") (pinfunction "LDAC_16") (pintype "input"))
      (node (ref "IC7") (pin "5") (pinfunction "VREFL_5") (pintype "bidirectional"))
      (node (ref "IC7") (pin "6") (pinfunction "GND_6") (pintype "power_in"))
      (node (ref "IC8") (pin "10") (pinfunction "+IN_10") (pintype "input"))
      (node (ref "IC8") (pin "2") (pinfunction "-IN_2") (pintype "input"))
      (node (ref "IC8") (pin "6") (pinfunction "-IN_6") (pintype "input"))
      (node (ref "IC9") (pin "11") (pinfunction "V-_11") (pintype "power_in"))
      (node (ref "IC9") (pin "13") (pinfunction "-IN_13") (pintype "input"))
      (node (ref "J1") (pin "P1") (pinfunction "1_P1") (pintype "passive"))
      (node (ref "J10") (pin "P1") (pinfunction "1_P1") (pintype "passive"))
      (node (ref "J11") (pin "P1") (pinfunction "1_P1") (pintype "passive"))
      (node (ref "J12") (pin "P1") (pinfunction "1_P1") (pintype "passive"))
      (node (ref "J2") (pin "P1") (pinfunction "1_P1") (pintype "passive"))
      (node (ref "J3") (pin "P1") (pinfunction "1_P1") (pintype "passive"))
      (node (ref "J4") (pin "P1") (pinfunction "1_P1") (pintype "passive"))
      (node (ref "J4") (pin "P2") (pinfunction "2_P2") (pintype "passive"))
      (node (ref "J5") (pin "P1") (pinfunction "1_P1") (pintype "passive"))
      (node (ref "J5") (pin "P2") (pinfunction "2_P2") (pintype "passive"))
      (node (ref "J6") (pin "P1") (pinfunction "1_P1") (pintype "passive"))
      (node (ref "J6") (pin "P2") (pinfunction "2_P2") (pintype "passive"))
      (node (ref "J7") (pin "P1") (pinfunction "1_P1") (pintype "passive"))
      (node (ref "J8") (pin "P1") (pinfunction "1_P1") (pintype "passive"))
      (node (ref "J9") (pin "P1") (pinfunction "1_P1") (pintype "passive"))
      (node (ref "JP1") (pin "3") (pinfunction "3_3") (pintype "passive"))
      (node (ref "JP1") (pin "4") (pinfunction "4_4") (pintype "passive"))
      (node (ref "JP1") (pin "5") (pinfunction "5_5") (pintype "passive"))
      (node (ref "JP1") (pin "6") (pinfunction "6_6") (pintype "passive"))
      (node (ref "JP1") (pin "7") (pinfunction "7_7") (pintype "passive"))
      (node (ref "JP1") (pin "8") (pinfunction "8_8") (pintype "passive"))
      (node (ref "JP2") (pin "1") (pinfunction "1_1") (pintype "passive"))
      (node (ref "POT_A") (pin "P$3") (pinfunction "A_P$3") (pintype "passive"))
      (node (ref "POT_B") (pin "P$3") (pinfunction "A_P$3") (pintype "passive"))
      (node (ref "POT_C") (pin "P$3") (pinfunction "A_P$3") (pintype "passive"))
      (node (ref "Q1") (pin "2") (pinfunction "LID1_2") (pintype "power_in"))
      (node (ref "Q1") (pin "4") (pinfunction "LID2_4") (pintype "power_in"))
      (node (ref "Q2") (pin "E") (pinfunction "E_E") (pintype "passive"))
      (node (ref "Q3") (pin "E") (pinfunction "E_E") (pintype "passive"))
      (node (ref "Q4") (pin "E") (pinfunction "E_E") (pintype "passive"))
      (node (ref "R20") (pin "1") (pinfunction "1_1") (pintype "passive"))
      (node (ref "R21") (pin "1") (pinfunction "1_1") (pintype "passive"))
      (node (ref "R23") (pin "1") (pinfunction "1_1") (pintype "passive"))
      (node (ref "R45") (pin "2") (pinfunction "2_2") (pintype "passive"))
      (node (ref "R46") (pin "2") (pinfunction "2_2") (pintype "passive"))
      (node (ref "R47") (pin "2") (pinfunction "2_2") (pintype "passive"))
      (node (ref "R48") (pin "2") (pinfunction "2_2") (pintype "passive"))
      (node (ref "R49") (pin "2") (pinfunction "2_2") (pintype "passive"))
      (node (ref "R5") (pin "2") (pinfunction "2_2") (pintype "passive"))
      (node (ref "R50") (pin "2") (pinfunction "2_2") (pintype "passive"))
      (node (ref "SLD_A") (pin "1") (pinfunction "A_1") (pintype "passive"))
      (node (ref "SLD_B") (pin "1") (pinfunction "A_1") (pintype "passive"))
      (node (ref "SLD_C") (pin "1") (pinfunction "A_1") (pintype "passive"))
      (node (ref "SW_A") (pin "1") (pinfunction "1_1") (pintype "passive"))
      (node (ref "SW_A") (pin "2") (pinfunction "2_2") (pintype "passive"))
      (node (ref "SW_B") (pin "1") (pinfunction "1_1") (pintype "passive"))
      (node (ref "SW_B") (pin "2") (pinfunction "2_2") (pintype "passive"))
      (node (ref "SW_C") (pin "1") (pinfunction "1_1") (pintype "passive"))
      (node (ref "SW_C") (pin "2") (pinfunction "2_2") (pintype "passive"))
      (node (ref "U$1") (pin "6") (pinfunction "P$6_6") (pintype "bidirectional"))
      (node (ref "U1") (pin "16") (pinfunction "VSS_2_16") (pintype "power_in"))
      (node (ref "U1") (pin "31") (pinfunction "BOOT0_31") (pintype "input"))
      (node (ref "U1") (pin "32") (pinfunction "VSS_1_32") (pintype "power_in"))
      (node (ref "U2") (pin "10") (pinfunction "+IN_10") (pintype "input"))
      (node (ref "U2") (pin "11") (pinfunction "V-_11") (pintype "power_in"))
      (node (ref "U2") (pin "12") (pinfunction "+IN_12") (pintype "input"))
      (node (ref "U2") (pin "3") (pinfunction "+IN_3") (pintype "input"))
      (node (ref "U2") (pin "5") (pinfunction "+IN_5") (pintype "input"))
    )
    (net (code "32") (name "GRN_A") (class "Default")
      (node (ref "A") (pin "GREEN_C") (pinfunction "GRN_GREEN_C") (pintype "bidirectional"))
      (node (ref "IC5") (pin "11") (pinfunction "OUT6_11") (pintype "bidirectional"))
    )
    (net (code "33") (name "GRN_B") (class "Default")
      (node (ref "B") (pin "GREEN_C") (pinfunction "GRN_GREEN_C") (pintype "bidirectional"))
      (node (ref "IC5") (pin "9") (pinfunction "OUT4_9") (pintype "bidirectional"))
    )
    (net (code "34") (name "GRN_C") (class "Default")
      (node (ref "C") (pin "GREEN_C") (pinfunction "GRN_GREEN_C") (pintype "bidirectional"))
      (node (ref "IC5") (pin "7") (pinfunction "OUT2_7") (pintype "bidirectional"))
    )
    (net (code "35") (name "LEDS_SS") (class "Default")
      (node (ref "IC5") (pin "4") (pinfunction "LAT_4") (pintype "bidirectional"))
      (node (ref "U1") (pin "11") (pinfunction "PA5_11") (pintype "bidirectional"))
    )
    (net (code "36") (name "NORMALIZATION_PROBE") (class "Default")
      (node (ref "D9") (pin "3") (pinfunction "AC_3") (pintype "passive"))
      (node (ref "R51") (pin "1") (pinfunction "1_1") (pintype "passive"))
      (node (ref "R52") (pin "1") (pinfunction "1_1") (pintype "passive"))
      (node (ref "R53") (pin "1") (pinfunction "1_1") (pintype "passive"))
      (node (ref "U1") (pin "10") (pinfunction "PA4_10") (pintype "bidirectional"))
    )
    (net (code "37") (name "N_U") (class "Default")
      (node (ref "U2") (pin "6") (pinfunction "-IN_6") (pintype "input"))
      (node (ref "U2") (pin "7") (pinfunction "OUT_7") (pintype "output"))
    )
    (net (code "38") (name "Net-(C1-Pad1)") (class "Default")
      (node (ref "C1") (pin "1") (pinfunction "1_1") (pintype "passive"))
      (node (ref "D1") (pin "C") (pinfunction "C_C") (pintype "passive"))
      (node (ref "L1") (pin "1") (pinfunction "1_1") (pintype "passive"))
      (node (ref "L2") (pin "2") (pinfunction "2_2") (pintype "passive"))
      (node (ref "L3") (pin "2") (pinfunction "2_2") (pintype "passive"))
    )
    (net (code "39") (name "Net-(C3-Pad1)") (class "Default")
      (node (ref "C3") (pin "1") (pinfunction "1_1") (pintype "passive"))
      (node (ref "IC2") (pin "2") (pinfunction "IN_2") (pintype "input"))
      (node (ref "IC2") (pin "4") (pinfunction "IN_4") (pintype "input"))
      (node (ref "L2") (pin "1") (pinfunction "1_1") (pintype "passive"))
    )
    (net (code "40") (name "Net-(C22-Pad2)") (class "Default")
      (node (ref "C22") (pin "2") (pinfunction "2_2") (pintype "passive"))
      (node (ref "Q1") (pin "1") (pinfunction "1_1") (pintype "passive"))
      (node (ref "R6") (pin "2") (pinfunction "2_2") (pintype "passive"))
    )
    (net (code "41") (name "Net-(D2-PadA)") (class "Default")
      (node (ref "D2") (pin "A") (pinfunction "A_A") (pintype "passive"))
      (node (ref "L4") (pin "2") (pinfunction "2_2") (pintype "passive"))
    )
    (net (code "42") (name "Net-(D3-PadC)") (class "Default")
      (node (ref "D3") (pin "C") (pinfunction "C_C") (pintype "passive"))
      (node (ref "Q2") (pin "B") (pinfunction "B_B") (pintype "passive"))
      (node (ref "R18") (pin "2") (pinfunction "2_2") (pintype "passive"))
      (node (ref "R23") (pin "2") (pinfunction "2_2") (pintype "passive"))
    )
    (net (code "43") (name "Net-(D4-PadC)") (class "Default")
      (node (ref "D4") (pin "C") (pinfunction "C_C") (pintype "passive"))
      (node (ref "Q3") (pin "B") (pinfunction "B_B") (pintype "passive"))
      (node (ref "R19") (pin "2") (pinfunction "2_2") (pintype "passive"))
      (node (ref "R20") (pin "2") (pinfunction "2_2") (pintype "passive"))
    )
    (net (code "44") (name "Net-(D5-PadC)") (class "Default")
      (node (ref "D5") (pin "C") (pinfunction "C_C") (pintype "passive"))
      (node (ref "Q4") (pin "B") (pinfunction "B_B") (pintype "passive"))
      (node (ref "R21") (pin "2") (pinfunction "2_2") (pintype "passive"))
      (node (ref "R22") (pin "2") (pinfunction "2_2") (pintype "passive"))
    )
    (net (code "45") (name "Net-(IC1-VI)") (class "Default")
      (node (ref "C5") (pin "1") (pinfunction "1_1") (pintype "passive"))
      (node (ref "IC1") (pin "1") (pinfunction "VI_1") (pintype "input"))
      (node (ref "L1") (pin "2") (pinfunction "2_2") (pintype "passive"))
    )
    (net (code "46") (name "Net-(IC4A-X0)") (class "Default")
      (node (ref "IC4") (pin "13") (pinfunction "X0_13") (pintype "bidirectional"))
      (node (ref "POT_C") (pin "P$2") (pinfunction "S_P$2") (pintype "passive"))
    )
    (net (code "47") (name "Net-(IC4A-X1)") (class "Default")
      (node (ref "IC4") (pin "14") (pinfunction "X1_14") (pintype "bidirectional"))
      (node (ref "SLD_C") (pin "2") (pinfunction "S_2") (pintype "passive"))
    )
    (net (code "48") (name "Net-(IC4A-X2)") (class "Default")
      (node (ref "IC4") (pin "15") (pinfunction "X2_15") (pintype "bidirectional"))
      (node (ref "SLD_B") (pin "2") (pinfunction "S_2") (pintype "passive"))
    )
    (net (code "49") (name "Net-(IC4A-X3)") (class "Default")
      (node (ref "IC4") (pin "12") (pinfunction "X3_12") (pintype "bidirectional"))
      (node (ref "POT_A") (pin "P$2") (pinfunction "S_P$2") (pintype "passive"))
    )
    (net (code "50") (name "Net-(IC4A-X4)") (class "Default")
      (node (ref "IC4") (pin "1") (pinfunction "X4_1") (pintype "bidirectional"))
      (node (ref "SLD_A") (pin "2") (pinfunction "S_2") (pintype "passive"))
    )
    (net (code "51") (name "Net-(IC4A-X5)") (class "Default")
      (node (ref "IC4") (pin "5") (pinfunction "X5_5") (pintype "bidirectional"))
      (node (ref "POT_B") (pin "P$2") (pinfunction "S_P$2") (pintype "passive"))
    )
    (net (code "52") (name "Net-(IC5-IREF)") (class "Default")
      (node (ref "IC5") (pin "23") (pinfunction "IREF_23") (pintype "bidirectional"))
      (node (ref "R5") (pin "1") (pinfunction "1_1") (pintype "passive"))
    )
    (net (code "53") (name "Net-(IC5-OUT7)") (class "Default")
      (node (ref "IC5") (pin "12") (pinfunction "OUT7_12") (pintype "bidirectional"))
      (node (ref "R16") (pin "2") (pinfunction "2_2") (pintype "passive"))
    )
    (net (code "54") (name "Net-(IC5-OUT8)") (class "Default")
      (node (ref "IC5") (pin "13") (pinfunction "OUT8_13") (pintype "bidirectional"))
      (node (ref "R17") (pin "2") (pinfunction "2_2") (pintype "passive"))
    )
    (net (code "55") (name "Net-(IC5-OUT9)") (class "Default")
      (node (ref "IC5") (pin "14") (pinfunction "OUT9_14") (pintype "bidirectional"))
      (node (ref "R15") (pin "2") (pinfunction "2_2") (pintype "passive"))
    )
    (net (code "56") (name "Net-(IC5-VCC)") (class "Default")
      (node (ref "C14") (pin "1") (pinfunction "1_1") (pintype "passive"))
      (node (ref "C15") (pin "1") (pinfunction "1_1") (pintype "passive"))
      (node (ref "IC5") (pin "24") (pinfunction "VCC_24") (pintype "bidirectional"))
      (node (ref "L5") (pin "1") (pinfunction "1_1") (pintype "passive"))
    )
    (net (code "57") (name "Net-(IC8A-+IN)") (class "Default")
      (node (ref "C33") (pin "1") (pinfunction "1_1") (pintype "passive"))
      (node (ref "IC8") (pin "3") (pinfunction "+IN_3") (pintype "input"))
      (node (ref "R30") (pin "1") (pinfunction "1_1") (pintype "passive"))
      (node (ref "R31") (pin "1") (pinfunction "1_1") (pintype "passive"))
      (node (ref "R32") (pin "2") (pinfunction "2_2") (pintype "passive"))
    )
    (net (code "58") (name "Net-(IC8A-OUT)") (class "Default")
      (node (ref "C33") (pin "2") (pinfunction "2_2") (pintype "passive"))
      (node (ref "IC8") (pin "1") (pinfunction "OUT_1") (pintype "output"))
      (node (ref "R43") (pin "2") (pinfunction "2_2") (pintype "passive"))
      (node (ref "U3") (pin "6") (pinfunction "-IN_6") (pintype "input"))
    )
    (net (code "59") (name "Net-(IC8B-+IN)") (class "Default")
      (node (ref "C32") (pin "1") (pinfunction "1_1") (pintype "passive"))
      (node (ref "IC8") (pin "5") (pinfunction "+IN_5") (pintype "input"))
      (node (ref "R27") (pin "1") (pinfunction "1_1") (pintype "passive"))
      (node (ref "R28") (pin "1") (pinfunction "1_1") (pintype "passive"))
      (node (ref "R29") (pin "2") (pinfunction "2_2") (pintype "passive"))
    )
    (net (code "60") (name "Net-(IC8B-OUT)") (class "Default")
      (node (ref "C32") (pin "2") (pinfunction "2_2") (pintype "passive"))
      (node (ref "IC8") (pin "7") (pinfunction "OUT_7") (pintype "output"))
      (node (ref "R42") (pin "2") (pinfunction "2_2") (pintype "passive"))
      (node (ref "U3") (pin "2") (pinfunction "-IN_2") (pintype "input"))
    )
    (net (code "61") (name "Net-(IC8C--IN)") (class "Default")
      (node (ref "C34") (pin "1") (pinfunction "1_1") (pintype "passive"))
      (node (ref "IC8") (pin "9") (pinfunction "-IN_9") (pintype "input"))
      (node (ref "R33") (pin "1") (pinfunction "1_1") (pintype "passive"))
      (node (ref "R34") (pin "1") (pinfunction "1_1") (pintype "passive"))
      (node (ref "R35") (pin "2") (pinfunction "2_2") (pintype "passive"))
    )
    (net (code "62") (name "Net-(IC8C-OUT)") (class "Default")
      (node (ref "C34") (pin "2") (pinfunction "2_2") (pintype "passive"))
      (node (ref "IC8") (pin "13") (pinfunction "-IN_13") (pintype "input"))
      (node (ref "IC8") (pin "8") (pinfunction "OUT_8") (pintype "output"))
      (node (ref "R40") (pin "2") (pinfunction "2_2") (pintype "passive"))
    )
    (net (code "63") (name "Net-(IC8D-+IN)") (class "Default")
      (node (ref "A_LED") (pin "2") (pinfunction "2_2") (pintype "bidirectional"))
      (node (ref "IC8") (pin "12") (pinfunction "+IN_12") (pintype "input"))
      (node (ref "R50") (pin "1") (pinfunction "1_1") (pintype "passive"))
    )
    (net (code "64") (name "Net-(IC8D-OUT)") (class "Default")
      (node (ref "A_LED") (pin "1") (pinfunction "1_1") (pintype "bidirectional"))
      (node (ref "IC8") (pin "14") (pinfunction "OUT_14") (pintype "output"))
    )
    (net (code "65") (name "Net-(IC9A-+IN)") (class "Default")
      (node (ref "IC9") (pin "3") (pinfunction "+IN_3") (pintype "input"))
      (node (ref "R44") (pin "2") (pinfunction "2_2") (pintype "passive"))
      (node (ref "R47") (pin "1") (pinfunction "1_1") (pintype "passive"))
    )
    (net (code "66") (name "Net-(IC9A--IN)") (class "Default")
      (node (ref "IC9") (pin "2") (pinfunction "-IN_2") (pintype "input"))
      (node (ref "R13") (pin "1") (pinfunction "1_1") (pintype "passive"))
    )
    (net (code "67") (name "Net-(IC9A-OUT)") (class "Default")
      (node (ref "IC9") (pin "1") (pinfunction "OUT_1") (pintype "output"))
      (node (ref "R39") (pin "2") (pinfunction "2_2") (pintype "passive"))
      (node (ref "R44") (pin "1") (pinfunction "1_1") (pintype "passive"))
    )
    (net (code "68") (name "Net-(IC9B-+IN)") (class "Default")
      (node (ref "IC9") (pin "5") (pinfunction "+IN_5") (pintype "input"))
      (node (ref "R41") (pin "2") (pinfunction "2_2") (pintype "passive"))
      (node (ref "R46") (pin "1") (pinfunction "1_1") (pintype "passive"))
    )
    (net (code "69") (name "Net-(IC9B--IN)") (class "Default")
      (node (ref "IC9") (pin "6") (pinfunction "-IN_6") (pintype "input"))
      (node (ref "R12") (pin "1") (pinfunction "1_1") (pintype "passive"))
    )
    (net (code "70") (name "Net-(IC9B-OUT)") (class "Default")
      (node (ref "IC9") (pin "7") (pinfunction "OUT_7") (pintype "output"))
      (node (ref "R38") (pin "2") (pinfunction "2_2") (pintype "passive"))
      (node (ref "R41") (pin "1") (pinfunction "1_1") (pintype "passive"))
    )
    (net (code "71") (name "Net-(IC9C-+IN)") (class "Default")
      (node (ref "IC9") (pin "10") (pinfunction "+IN_10") (pintype "input"))
      (node (ref "R11") (pin "1") (pinfunction "1_1") (pintype "passive"))
    )
    (net (code "72") (name "Net-(IC9C--IN)") (class "Default")
      (node (ref "IC9") (pin "9") (pinfunction "-IN_9") (pintype "input"))
      (node (ref "R36") (pin "2") (pinfunction "2_2") (pintype "passive"))
      (node (ref "R45") (pin "1") (pinfunction "1_1") (pintype "passive"))
    )
    (net (code "73") (name "Net-(IC9C-OUT)") (class "Default")
      (node (ref "IC9") (pin "8") (pinfunction "OUT_8") (pintype "output"))
      (node (ref "R36") (pin "1") (pinfunction "1_1") (pintype "passive"))
      (node (ref "R37") (pin "2") (pinfunction "2_2") (pintype "passive"))
    )
    (net (code "74") (name "Net-(IC9D-+IN)") (class "Default")
      (node (ref "IC9") (pin "12") (pinfunction "+IN_12") (pintype "input"))
      (node (ref "IC9") (pin "14") (pinfunction "OUT_14") (pintype "output"))
    )
    (net (code "75") (name "Net-(J1-2)") (class "Default")
      (node (ref "J1") (pin "P2") (pinfunction "2_P2") (pintype "passive"))
      (node (ref "R51") (pin "2") (pinfunction "2_2") (pintype "passive"))
    )
    (net (code "76") (name "Net-(J2-2)") (class "Default")
      (node (ref "J2") (pin "P2") (pinfunction "2_P2") (pintype "passive"))
      (node (ref "R52") (pin "2") (pinfunction "2_2") (pintype "passive"))
    )
    (net (code "77") (name "Net-(J3-2)") (class "Default")
      (node (ref "J3") (pin "P2") (pinfunction "2_P2") (pintype "passive"))
      (node (ref "R53") (pin "2") (pinfunction "2_2") (pintype "passive"))
    )
    (net (code "78") (name "Net-(J4-3)") (class "Default")
      (node (ref "J4") (pin "P3") (pinfunction "3_P3") (pintype "passive"))
      (node (ref "R24") (pin "2") (pinfunction "2_2") (pintype "passive"))
    )
    (net (code "79") (name "Net-(J5-3)") (class "Default")
      (node (ref "J5") (pin "P3") (pinfunction "3_P3") (pintype "passive"))
      (node (ref "R25") (pin "2") (pinfunction "2_2") (pintype "passive"))
    )
    (net (code "80") (name "Net-(J6-3)") (class "Default")
      (node (ref "J6") (pin "P3") (pinfunction "3_P3") (pintype "passive"))
      (node (ref "R26") (pin "2") (pinfunction "2_2") (pintype "passive"))
    )
    (net (code "81") (name "Net-(Q1B-2)") (class "Default")
      (node (ref "C21") (pin "2") (pinfunction "2_2") (pintype "passive"))
      (node (ref "Q1") (pin "3") (pinfunction "2_3") (pintype "passive"))
      (node (ref "R9") (pin "2") (pinfunction "2_2") (pintype "passive"))
    )
    (net (code "82") (name "Net-(SLD_AA-C)") (class "Default")
      (node (ref "R16") (pin "1") (pinfunction "1_1") (pintype "passive"))
      (node (ref "SLD_A") (pin "E") (pinfunction "C_E") (pintype "passive"))
    )
    (net (code "83") (name "Net-(SLD_BA-C)") (class "Default")
      (node (ref "R17") (pin "1") (pinfunction "1_1") (pintype "passive"))
      (node (ref "SLD_B") (pin "E") (pinfunction "C_E") (pintype "passive"))
    )
    (net (code "84") (name "Net-(SLD_CA-C)") (class "Default")
      (node (ref "R15") (pin "1") (pinfunction "1_1") (pintype "passive"))
      (node (ref "SLD_C") (pin "E") (pinfunction "C_E") (pintype "passive"))
    )
    (net (code "85") (name "Net-(U1-PF0{slash}OSC_IN)") (class "Default")
      (node (ref "R9") (pin "1") (pinfunction "1_1") (pintype "passive"))
      (node (ref "U1") (pin "2") (pinfunction "PF0/OSC_IN_2") (pintype "bidirectional"))
    )
    (net (code "86") (name "Net-(U1-PF1{slash}OSC_OUT)") (class "Default")
      (node (ref "R6") (pin "1") (pinfunction "1_1") (pintype "passive"))
      (node (ref "U1") (pin "3") (pinfunction "PF1/OSC_OUT_3") (pintype "bidirectional"))
    )
    (net (code "87") (name "Net-(U2A--IN)") (class "Default")
      (node (ref "C30") (pin "1") (pinfunction "1_1") (pintype "passive"))
      (node (ref "R14") (pin "2") (pinfunction "2_2") (pintype "passive"))
      (node (ref "R2") (pin "1") (pinfunction "1_1") (pintype "passive"))
      (node (ref "R26") (pin "1") (pinfunction "1_1") (pintype "passive"))
      (node (ref "U2") (pin "2") (pinfunction "-IN_2") (pintype "input"))
    )
    (net (code "88") (name "Net-(U2C--IN)") (class "Default")
      (node (ref "C23") (pin "1") (pinfunction "1_1") (pintype "passive"))
      (node (ref "R25") (pin "1") (pinfunction "1_1") (pintype "passive"))
      (node (ref "R3") (pin "1") (pinfunction "1_1") (pintype "passive"))
      (node (ref "R7") (pin "2") (pinfunction "2_2") (pintype "passive"))
      (node (ref "U2") (pin "9") (pinfunction "-IN_9") (pintype "input"))
    )
    (net (code "89") (name "Net-(U2D--IN)") (class "Default")
      (node (ref "C24") (pin "1") (pinfunction "1_1") (pintype "passive"))
      (node (ref "R24") (pin "1") (pinfunction "1_1") (pintype "passive"))
      (node (ref "R4") (pin "1") (pinfunction "1_1") (pintype "passive"))
      (node (ref "R8") (pin "2") (pinfunction "2_2") (pintype "passive"))
      (node (ref "U2") (pin "13") (pinfunction "-IN_13") (pintype "input"))
    )
    (net (code "90") (name "Net-(U3A-+IN)") (class "Default")
      (node (ref "B_LED") (pin "2") (pinfunction "2_2") (pintype "bidirectional"))
      (node (ref "R49") (pin "1") (pinfunction "1_1") (pintype "passive"))
      (node (ref "U3") (pin "3") (pinfunction "+IN_3") (pintype "input"))
    )
    (net (code "91") (name "Net-(U3B-+IN)") (class "Default")
      (node (ref "C_LED") (pin "2") (pinfunction "2_2") (pintype "bidirectional"))
      (node (ref "R48") (pin "1") (pinfunction "1_1") (pintype "passive"))
      (node (ref "U3") (pin "5") (pinfunction "+IN_5") (pintype "input"))
    )
    (net (code "92") (name "POTS_ADDR_A") (class "Default")
      (node (ref "IC4") (pin "11") (pinfunction "A_11") (pintype "input"))
      (node (ref "U1") (pin "13") (pinfunction "PA7_13") (pintype "bidirectional"))
    )
    (net (code "93") (name "POTS_ADDR_B") (class "Default")
      (node (ref "IC4") (pin "10") (pinfunction "B_10") (pintype "input"))
      (node (ref "U1") (pin "18") (pinfunction "PA8_18") (pintype "bidirectional"))
    )
    (net (code "94") (name "POTS_ADDR_C") (class "Default")
      (node (ref "IC4") (pin "9") (pinfunction "C_9") (pintype "input"))
      (node (ref "U1") (pin "19") (pinfunction "PA9_19") (pintype "bidirectional"))
    )
    (net (code "95") (name "RED_A") (class "Default")
      (node (ref "A") (pin "RED_C") (pinfunction "RED_RED_C") (pintype "bidirectional"))
      (node (ref "IC5") (pin "10") (pinfunction "OUT5_10") (pintype "bidirectional"))
    )
    (net (code "96") (name "RED_B") (class "Default")
      (node (ref "B") (pin "RED_C") (pinfunction "RED_RED_C") (pintype "bidirectional"))
      (node (ref "IC5") (pin "8") (pinfunction "OUT3_8") (pintype "bidirectional"))
    )
    (net (code "97") (name "RED_C") (class "Default")
      (node (ref "C") (pin "RED_C") (pinfunction "RED_RED_C") (pintype "bidirectional"))
      (node (ref "IC5") (pin "6") (pinfunction "OUT1_6") (pintype "bidirectional"))
    )
    (net (code "98") (name "RESET") (class "Default")
      (node (ref "C28") (pin "1") (pinfunction "1_1") (pintype "passive"))
      (node (ref "JP2") (pin "4") (pinfunction "4_4") (pintype "passive"))
      (node (ref "R10") (pin "2") (pinfunction "2_2") (pintype "passive"))
      (node (ref "U1") (pin "4") (pinfunction "NRST_4") (pintype "bidirectional"))
    )
    (net (code "99") (name "SPI_MOSI") (class "Default")
      (node (ref "IC5") (pin "2") (pinfunction "SIN_2") (pintype "bidirectional"))
      (node (ref "IC7") (pin "11") (pinfunction "IN_11") (pintype "input"))
      (node (ref "U1") (pin "28") (pinfunction "PB5_28") (pintype "bidirectional"))
    )
    (net (code "100") (name "SPI_SCK") (class "Default")
      (node (ref "IC5") (pin "3") (pinfunction "SCLK_3") (pintype "bidirectional"))
      (node (ref "IC7") (pin "10") (pinfunction "SCK_10") (pintype "input"))
      (node (ref "U1") (pin "26") (pinfunction "PB3_26") (pintype "bidirectional"))
    )
    (net (code "101") (name "SWCLK") (class "Default")
      (node (ref "JP2") (pin "3") (pinfunction "3_3") (pintype "passive"))
      (node (ref "U1") (pin "24") (pinfunction "PA14_24") (pintype "bidirectional"))
    )
    (net (code "102") (name "SWDIO") (class "Default")
      (node (ref "JP2") (pin "2") (pinfunction "2_2") (pintype "passive"))
      (node (ref "U1") (pin "23") (pinfunction "PA13_23") (pintype "bidirectional"))
    )
    (net (code "103") (name "SW_MODE_A") (class "Default")
      (node (ref "SW_A") (pin "3") (pinfunction "3_3") (pintype "passive"))
      (node (ref "SW_A") (pin "4") (pinfunction "4_4") (pintype "passive"))
      (node (ref "U1") (pin "27") (pinfunction "PB4_27") (pintype "bidirectional"))
    )
    (net (code "104") (name "SW_MODE_B") (class "Default")
      (node (ref "SW_B") (pin "3") (pinfunction "3_3") (pintype "passive"))
      (node (ref "SW_B") (pin "4") (pinfunction "4_4") (pintype "passive"))
      (node (ref "U1") (pin "29") (pinfunction "PB6_29") (pintype "bidirectional"))
    )
    (net (code "105") (name "SW_MODE_C") (class "Default")
      (node (ref "SW_C") (pin "3") (pinfunction "3_3") (pintype "passive"))
      (node (ref "SW_C") (pin "4") (pinfunction "4_4") (pintype "passive"))
      (node (ref "U1") (pin "30") (pinfunction "PB7_30") (pintype "bidirectional"))
    )
    (net (code "106") (name "VCC") (class "Default")
      (node (ref "C2") (pin "1") (pinfunction "1_1") (pintype "passive"))
      (node (ref "C31") (pin "1") (pinfunction "1_1") (pintype "passive"))
      (node (ref "C35") (pin "1") (pinfunction "1_1") (pintype "passive"))
      (node (ref "C36") (pin "1") (pinfunction "1_1") (pintype "passive"))
      (node (ref "C4") (pin "1") (pinfunction "1_1") (pintype "passive"))
      (node (ref "IC8") (pin "4") (pinfunction "V+_4") (pintype "power_in"))
      (node (ref "IC9") (pin "4") (pinfunction "V+_4") (pintype "power_in"))
      (node (ref "L3") (pin "1") (pinfunction "1_1") (pintype "passive"))
      (node (ref "U$1") (pin "1") (pinfunction "P$1_1") (pintype "bidirectional"))
      (node (ref "U3") (pin "8") (pinfunction "V+_8") (pintype "power_in"))
    )
    (net (code "107") (name "VEE") (class "Default")
      (node (ref "C10") (pin "2") (pinfunction "2_2") (pintype "passive"))
      (node (ref "C25") (pin "2") (pinfunction "2_2") (pintype "passive"))
      (node (ref "C37") (pin "2") (pinfunction "2_2") (pintype "passive"))
      (node (ref "C9") (pin "2") (pinfunction "2_2") (pintype "passive"))
      (node (ref "IC8") (pin "11") (pinfunction "V-_11") (pintype "power_in"))
      (node (ref "L4") (pin "1") (pinfunction "1_1") (pintype "passive"))
      (node (ref "R1") (pin "1") (pinfunction "1_1") (pintype "passive"))
      (node (ref "U$1") (pin "2") (pinfunction "P$2_2") (pintype "bidirectional"))
      (node (ref "U3") (pin "4") (pinfunction "V-_4") (pintype "power_in"))
    )
    (net (code "108") (name "VREF") (class "Default")
      (node (ref "C41") (pin "1") (pinfunction "1_1") (pintype "passive"))
      (node (ref "IC7") (pin "3") (pinfunction "VREFH_3") (pintype "bidirectional"))
    )
    (net (code "109") (name "unconnected-(IC4A-X6-Pad2)") (class "Default")
      (node (ref "IC4") (pin "2") (pinfunction "X6_2") (pintype "bidirectional"))
    )
    (net (code "110") (name "unconnected-(IC4A-X7-Pad4)") (class "Default")
      (node (ref "IC4") (pin "4") (pinfunction "X7_4") (pintype "bidirectional"))
    )
    (net (code "111") (name "unconnected-(IC5-OUT0-Pad5)") (class "Default")
      (node (ref "IC5") (pin "5") (pinfunction "OUT0_5") (pintype "bidirectional"))
    )
    (net (code "112") (name "unconnected-(IC5-OUT10-Pad15)") (class "Default")
      (node (ref "IC5") (pin "15") (pinfunction "OUT10_15") (pintype "bidirectional"))
    )
    (net (code "113") (name "unconnected-(IC5-OUT11-Pad16)") (class "Default")
      (node (ref "IC5") (pin "16") (pinfunction "OUT11_16") (pintype "bidirectional"))
    )
    (net (code "114") (name "unconnected-(IC5-OUT12-Pad17)") (class "Default")
      (node (ref "IC5") (pin "17") (pinfunction "OUT12_17") (pintype "bidirectional"))
    )
    (net (code "115") (name "unconnected-(IC5-OUT13-Pad18)") (class "Default")
      (node (ref "IC5") (pin "18") (pinfunction "OUT13_18") (pintype "bidirectional"))
    )
    (net (code "116") (name "unconnected-(IC5-OUT14-Pad19)") (class "Default")
      (node (ref "IC5") (pin "19") (pinfunction "OUT14_19") (pintype "bidirectional"))
    )
    (net (code "117") (name "unconnected-(IC5-OUT15-Pad20)") (class "Default")
      (node (ref "IC5") (pin "20") (pinfunction "OUT15_20") (pintype "bidirectional"))
    )
    (net (code "118") (name "unconnected-(IC5-SOUT-Pad22)") (class "Default")
      (node (ref "IC5") (pin "22") (pinfunction "SOUT_22") (pintype "bidirectional"))
    )
    (net (code "119") (name "unconnected-(IC7-OUTD-Pad8)") (class "Default")
      (node (ref "IC7") (pin "8") (pinfunction "OUTD_8") (pintype "output"))
    )
    (net (code "120") (name "unconnected-(J7-2-PadP2)") (class "Default")
      (node (ref "J7") (pin "P2") (pinfunction "2_P2") (pintype "passive"))
    )
    (net (code "121") (name "unconnected-(J8-2-PadP2)") (class "Default")
      (node (ref "J8") (pin "P2") (pinfunction "2_P2") (pintype "passive"))
    )
    (net (code "122") (name "unconnected-(J9-2-PadP2)") (class "Default")
      (node (ref "J9") (pin "P2") (pinfunction "2_P2") (pintype "passive"))
    )
    (net (code "123") (name "unconnected-(J10-2-PadP2)") (class "Default")
      (node (ref "J10") (pin "P2") (pinfunction "2_P2") (pintype "passive"))
    )
    (net (code "124") (name "unconnected-(J11-2-PadP2)") (class "Default")
      (node (ref "J11") (pin "P2") (pinfunction "2_P2") (pintype "passive"))
    )
    (net (code "125") (name "unconnected-(J12-2-PadP2)") (class "Default")
      (node (ref "J12") (pin "P2") (pinfunction "2_P2") (pintype "passive"))
    )
  )
)
